# iMX233-OLINUXINO-MINI_Rev_C.net
KiCad netlist of a schematic drawn in EAGLE
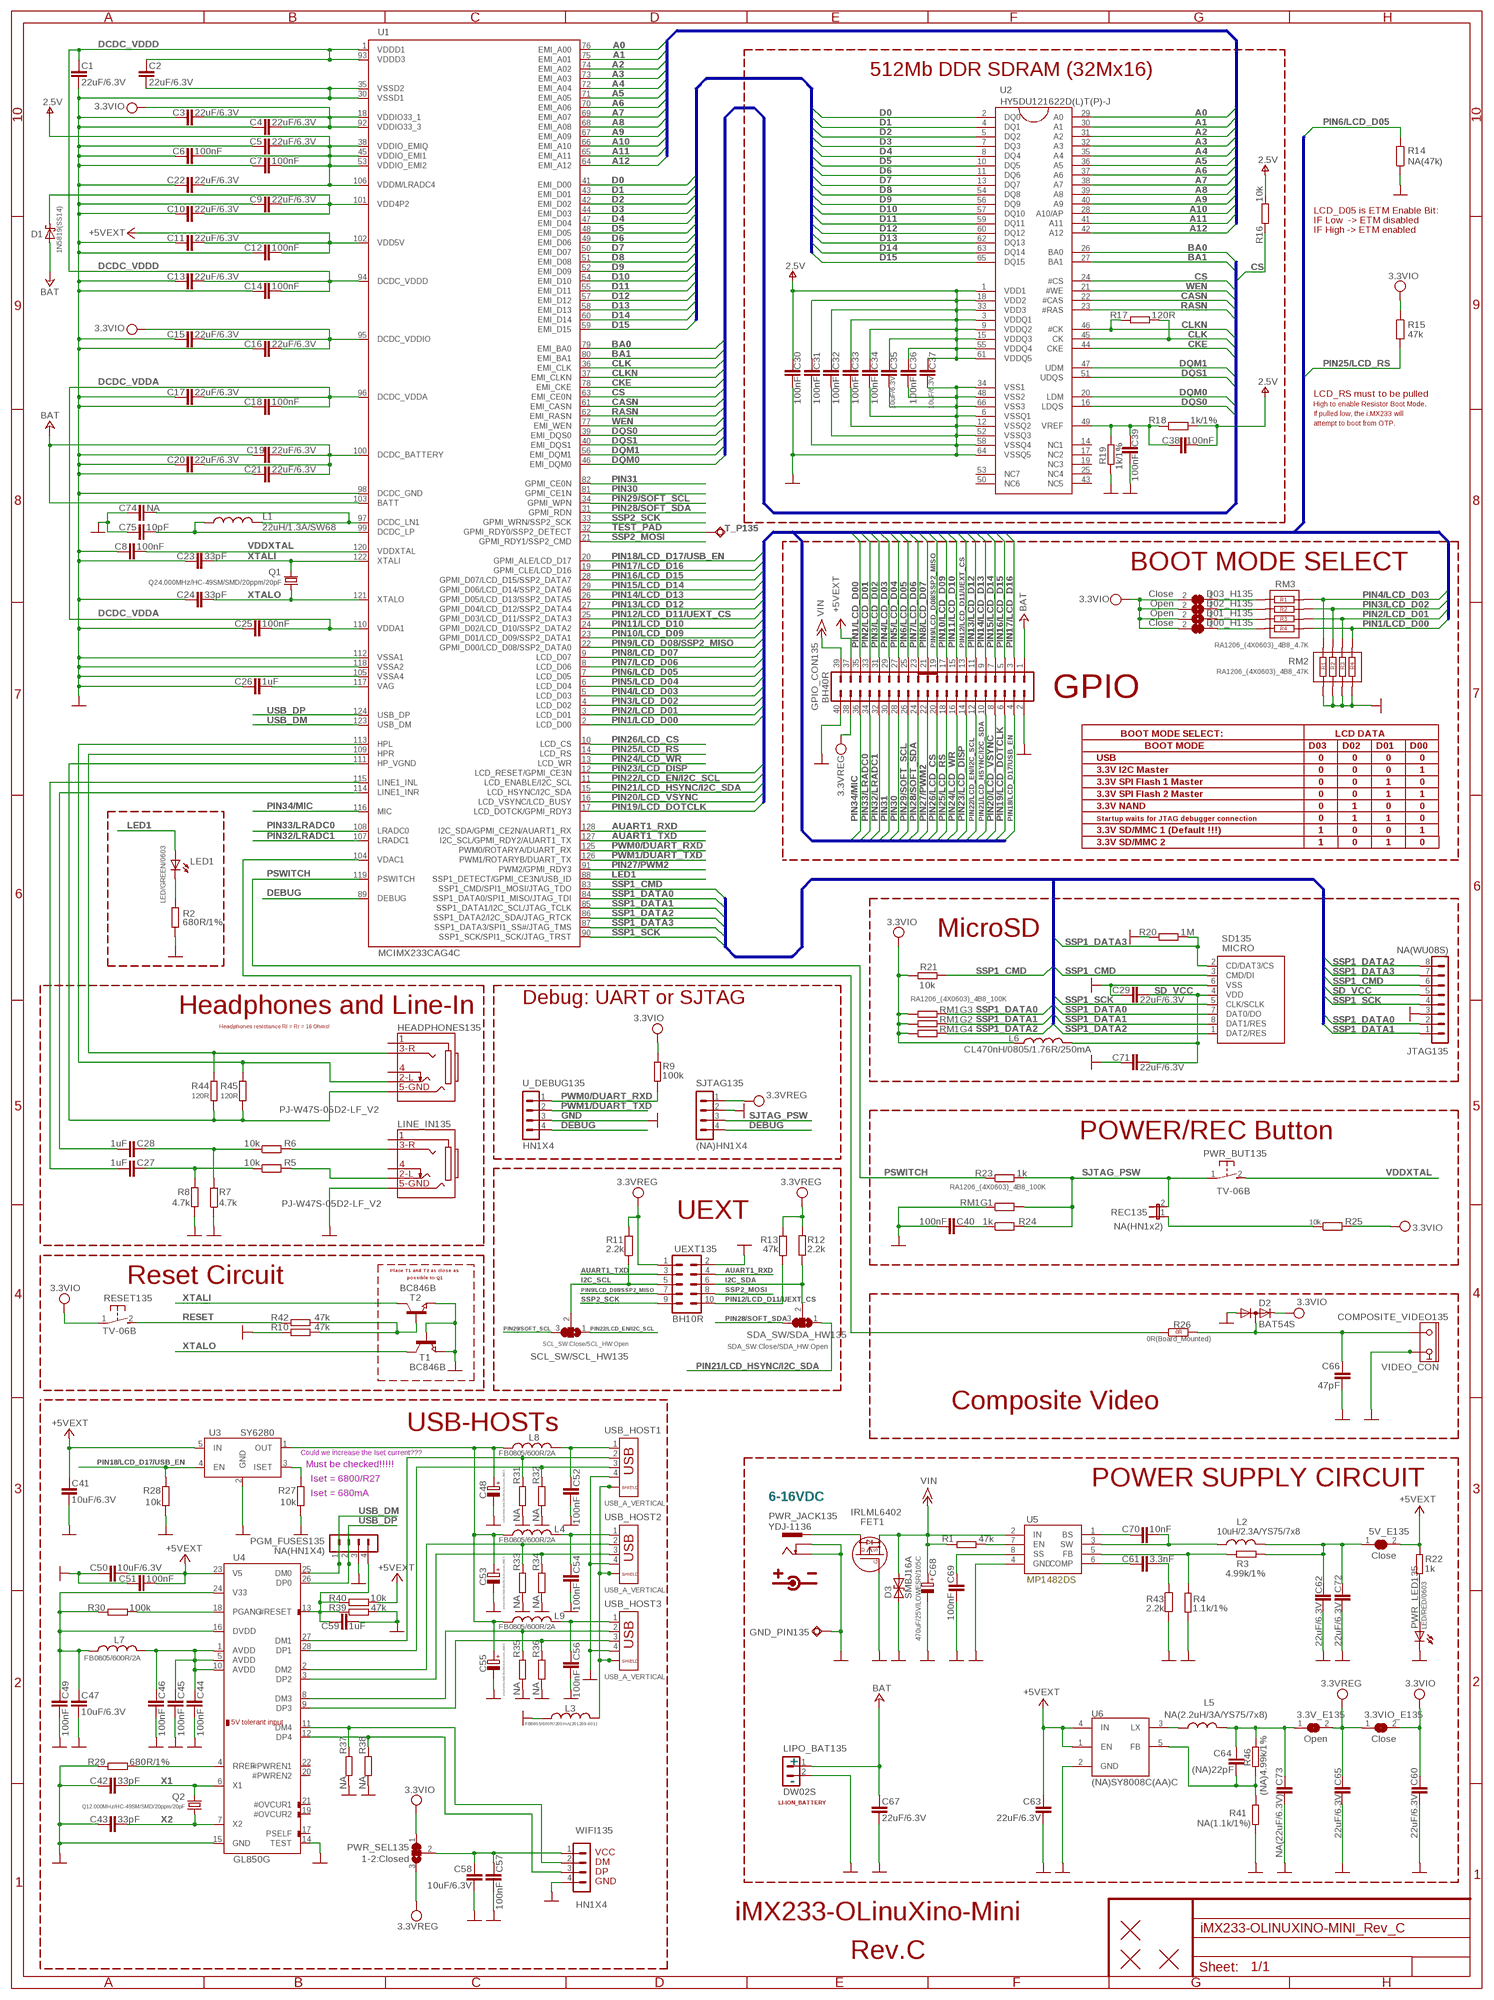
[diagram p0: schematic, sheet 1]

(export (version "E")
  (design (tool "Eeschema 10.0.6"))
  (components
    (comp (ref "3.3VIO_E135")
      (value "Close")
      (footprint "eagle-import:SJ_1_SMALLER")
      (libsource (lib "eagle-import") (part "SJSJ_SMALLER"))
    )
    (comp (ref "3.3V_E135")
      (value "Open")
      (footprint "eagle-import:SJ_1_SMALLER")
      (libsource (lib "eagle-import") (part "SJSJ_SMALLER"))
    )
    (comp (ref "5V_E135")
      (value "Close")
      (footprint "eagle-import:SJ_1_SMALLER_CLOSE")
      (libsource (lib "eagle-import") (part "SJSJ_1_SMALLER_CLOSE"))
    )
    (comp (ref "C1")
      (value "22uF/6.3V")
      (footprint "eagle-import:C0805_5MIL_DWS")
      (libsource (lib "eagle-import") (part "C-EUC0805_5MIL_DWS"))
    )
    (comp (ref "C2")
      (value "22uF/6.3V")
      (footprint "eagle-import:C0805_5MIL_DWS")
      (libsource (lib "eagle-import") (part "C-EUC0805_5MIL_DWS"))
    )
    (comp (ref "C3")
      (value "22uF/6.3V")
      (footprint "eagle-import:C0805_5MIL_DWS")
      (libsource (lib "eagle-import") (part "C-EUC0805_5MIL_DWS"))
    )
    (comp (ref "C4")
      (value "22uF/6.3V")
      (footprint "eagle-import:C0805_5MIL_DWS")
      (libsource (lib "eagle-import") (part "C-EUC0805_5MIL_DWS"))
    )
    (comp (ref "C5")
      (value "22uF/6.3V")
      (footprint "eagle-import:C0805_5MIL_DWS")
      (libsource (lib "eagle-import") (part "C-EUC0805_5MIL_DWS"))
    )
    (comp (ref "C6")
      (value "100nF")
      (footprint "eagle-import:C0603_DWS")
      (libsource (lib "eagle-import") (part "C-EUC0603_DWS"))
    )
    (comp (ref "C7")
      (value "100nF")
      (footprint "eagle-import:C0603_DWS")
      (libsource (lib "eagle-import") (part "C-EUC0603_DWS"))
    )
    (comp (ref "C8")
      (value "100nF")
      (footprint "eagle-import:C0603_DWS")
      (libsource (lib "eagle-import") (part "C-EUC0603_DWS"))
    )
    (comp (ref "C9")
      (value "22uF/6.3V")
      (footprint "eagle-import:C0805_5MIL_DWS")
      (libsource (lib "eagle-import") (part "C-EUC0805_5MIL_DWS"))
    )
    (comp (ref "C10")
      (value "22uF/6.3V")
      (footprint "eagle-import:C0805_5MIL_DWS")
      (libsource (lib "eagle-import") (part "C-EUC0805_5MIL_DWS"))
    )
    (comp (ref "C11")
      (value "22uF/6.3V")
      (footprint "eagle-import:C0805_5MIL_DWS")
      (libsource (lib "eagle-import") (part "C-EUC0805_5MIL_DWS"))
    )
    (comp (ref "C12")
      (value "100nF")
      (footprint "eagle-import:C0603_DWS")
      (libsource (lib "eagle-import") (part "C-EUC0603_DWS"))
    )
    (comp (ref "C13")
      (value "22uF/6.3V")
      (footprint "eagle-import:C0805_5MIL_DWS")
      (libsource (lib "eagle-import") (part "C-EUC0805_5MIL_DWS"))
    )
    (comp (ref "C14")
      (value "100nF")
      (footprint "eagle-import:C0603_DWS")
      (libsource (lib "eagle-import") (part "C-EUC0603_DWS"))
    )
    (comp (ref "C15")
      (value "22uF/6.3V")
      (footprint "eagle-import:C0805_5MIL_DWS")
      (libsource (lib "eagle-import") (part "C-EUC0805_5MIL_DWS"))
    )
    (comp (ref "C16")
      (value "22uF/6.3V")
      (footprint "eagle-import:C0805_5MIL_DWS")
      (libsource (lib "eagle-import") (part "C-EUC0805_5MIL_DWS"))
    )
    (comp (ref "C17")
      (value "22uF/6.3V")
      (footprint "eagle-import:C0805_5MIL_DWS")
      (libsource (lib "eagle-import") (part "C-EUC0805_5MIL_DWS"))
    )
    (comp (ref "C18")
      (value "100nF")
      (footprint "eagle-import:C0603_DWS")
      (libsource (lib "eagle-import") (part "C-EUC0603_DWS"))
    )
    (comp (ref "C19")
      (value "22uF/6.3V")
      (footprint "eagle-import:C0805_5MIL_DWS")
      (libsource (lib "eagle-import") (part "C-EUC0805_5MIL_DWS"))
    )
    (comp (ref "C20")
      (value "22uF/6.3V")
      (footprint "eagle-import:C0805_5MIL_DWS")
      (libsource (lib "eagle-import") (part "C-EUC0805_5MIL_DWS"))
    )
    (comp (ref "C21")
      (value "22uF/6.3V")
      (footprint "eagle-import:C0805_5MIL_DWS")
      (libsource (lib "eagle-import") (part "C-EUC0805_5MIL_DWS"))
    )
    (comp (ref "C22")
      (value "22uF/6.3V")
      (footprint "eagle-import:C0805_5MIL_DWS")
      (libsource (lib "eagle-import") (part "C-EUC0805_5MIL_DWS"))
    )
    (comp (ref "C23")
      (value "33pF")
      (footprint "eagle-import:C0603_DWS")
      (libsource (lib "eagle-import") (part "C-EUC0603_DWS"))
    )
    (comp (ref "C24")
      (value "33pF")
      (footprint "eagle-import:C0603_DWS")
      (libsource (lib "eagle-import") (part "C-EUC0603_DWS"))
    )
    (comp (ref "C25")
      (value "100nF")
      (footprint "eagle-import:C0603_DWS")
      (libsource (lib "eagle-import") (part "C-EUC0603_DWS"))
    )
    (comp (ref "C26")
      (value "1uF")
      (footprint "eagle-import:C0603_DWS")
      (libsource (lib "eagle-import") (part "C-EUC0603_DWS"))
    )
    (comp (ref "C27")
      (value "1uF")
      (footprint "eagle-import:C0603_DWS")
      (libsource (lib "eagle-import") (part "C-EUC0603_DWS"))
    )
    (comp (ref "C28")
      (value "1uF")
      (footprint "eagle-import:C0603_DWS")
      (libsource (lib "eagle-import") (part "C-EUC0603_DWS"))
    )
    (comp (ref "C29")
      (value "22uF/6.3V")
      (footprint "eagle-import:C0805_5MIL_DWS")
      (libsource (lib "eagle-import") (part "C-EUC0805_5MIL_DWS"))
    )
    (comp (ref "C30")
      (value "100nF")
      (footprint "eagle-import:C0603_DWS")
      (libsource (lib "eagle-import") (part "C-EUC0603_DWS"))
    )
    (comp (ref "C31")
      (value "100nF")
      (footprint "eagle-import:C0603_DWS")
      (libsource (lib "eagle-import") (part "C-EUC0603_DWS"))
    )
    (comp (ref "C32")
      (value "100nF")
      (footprint "eagle-import:C0603_DWS")
      (libsource (lib "eagle-import") (part "C-EUC0603_DWS"))
    )
    (comp (ref "C33")
      (value "100nF")
      (footprint "eagle-import:C0603_DWS")
      (libsource (lib "eagle-import") (part "C-EUC0603_DWS"))
    )
    (comp (ref "C34")
      (value "100nF")
      (footprint "eagle-import:C0603_DWS")
      (libsource (lib "eagle-import") (part "C-EUC0603_DWS"))
    )
    (comp (ref "C35")
      (value "10uF/6.3V")
      (footprint "eagle-import:C0603_DWS")
      (libsource (lib "eagle-import") (part "C-EUC0603_DWS"))
    )
    (comp (ref "C36")
      (value "100nF")
      (footprint "eagle-import:C0603_DWS")
      (libsource (lib "eagle-import") (part "C-EUC0603_DWS"))
    )
    (comp (ref "C37")
      (value "10uF/6.3V")
      (footprint "eagle-import:C0603_DWS")
      (libsource (lib "eagle-import") (part "C-EUC0603_DWS"))
    )
    (comp (ref "C38")
      (value "100nF")
      (footprint "eagle-import:C0603_DWS")
      (libsource (lib "eagle-import") (part "C-EUC0603_DWS"))
    )
    (comp (ref "C39")
      (value "100nF")
      (footprint "eagle-import:C0603_DWS")
      (libsource (lib "eagle-import") (part "C-EUC0603_DWS"))
    )
    (comp (ref "C40")
      (value "100nF")
      (footprint "eagle-import:C0603_DWS")
      (libsource (lib "eagle-import") (part "C-EUC0603_DWS"))
    )
    (comp (ref "C41")
      (value "10uF/6.3V")
      (footprint "eagle-import:C0603_DWS")
      (libsource (lib "eagle-import") (part "C-EUC0603_DWS"))
    )
    (comp (ref "C42")
      (value "33pF")
      (footprint "eagle-import:C0603_DWS")
      (libsource (lib "eagle-import") (part "C-EUC0603_DWS"))
    )
    (comp (ref "C43")
      (value "33pF")
      (footprint "eagle-import:C0603_DWS")
      (libsource (lib "eagle-import") (part "C-EUC0603_DWS"))
    )
    (comp (ref "C44")
      (value "100nF")
      (footprint "eagle-import:C0603_DWS")
      (libsource (lib "eagle-import") (part "C-EUC0603_DWS"))
    )
    (comp (ref "C45")
      (value "100nF")
      (footprint "eagle-import:C0603_DWS")
      (libsource (lib "eagle-import") (part "C-EUC0603_DWS"))
    )
    (comp (ref "C46")
      (value "100nF")
      (footprint "eagle-import:C0603_DWS")
      (libsource (lib "eagle-import") (part "C-EUC0603_DWS"))
    )
    (comp (ref "C47")
      (value "10uF/6.3V")
      (footprint "eagle-import:C0603_DWS")
      (libsource (lib "eagle-import") (part "C-EUC0603_DWS"))
    )
    (comp (ref "C48")
      (value "100uF/16V/LOWESR/105C/6.3x11mm_RM2.5")
      (footprint "eagle-import:E2,5-6,3")
      (libsource (lib "eagle-import") (part "CPOL-EUE2.5-6.3"))
    )
    (comp (ref "C49")
      (value "100nF")
      (footprint "eagle-import:C0603_DWS")
      (libsource (lib "eagle-import") (part "C-EUC0603_DWS"))
    )
    (comp (ref "C50")
      (value "10uF/6.3V")
      (footprint "eagle-import:C0603_DWS")
      (libsource (lib "eagle-import") (part "C-EUC0603_DWS"))
    )
    (comp (ref "C51")
      (value "100nF")
      (footprint "eagle-import:C0603_DWS")
      (libsource (lib "eagle-import") (part "C-EUC0603_DWS"))
    )
    (comp (ref "C52")
      (value "100nF")
      (footprint "eagle-import:C0603_DWS")
      (libsource (lib "eagle-import") (part "C-EUC0603_DWS"))
    )
    (comp (ref "C53")
      (value "100uF/16V/LOWESR/105C/6.3x11mm_RM2.5")
      (footprint "eagle-import:E2,5-6,3")
      (libsource (lib "eagle-import") (part "CPOL-EUE2.5-6.3"))
    )
    (comp (ref "C54")
      (value "100nF")
      (footprint "eagle-import:C0603_DWS")
      (libsource (lib "eagle-import") (part "C-EUC0603_DWS"))
    )
    (comp (ref "C55")
      (value "100uF/16V/LOWESR/105C/6.3x11mm_RM2.5")
      (footprint "eagle-import:E2,5-6,3")
      (libsource (lib "eagle-import") (part "CPOL-EUE2.5-6.3"))
    )
    (comp (ref "C56")
      (value "100nF")
      (footprint "eagle-import:C0603_DWS")
      (libsource (lib "eagle-import") (part "C-EUC0603_DWS"))
    )
    (comp (ref "C57")
      (value "100nF")
      (footprint "eagle-import:C0603_DWS")
      (libsource (lib "eagle-import") (part "C-EUC0603_DWS"))
    )
    (comp (ref "C58")
      (value "10uF/6.3V")
      (footprint "eagle-import:C0603_DWS")
      (libsource (lib "eagle-import") (part "C-EUC0603_DWS"))
    )
    (comp (ref "C59")
      (value "1uF")
      (footprint "eagle-import:C0603_DWS")
      (libsource (lib "eagle-import") (part "C-EUC0603_DWS"))
    )
    (comp (ref "C60")
      (value "22uF/6.3V")
      (footprint "eagle-import:C0805_5MIL_DWS")
      (libsource (lib "eagle-import") (part "C-EUC0805_5MIL_DWS"))
    )
    (comp (ref "C61")
      (value "3.3nF")
      (footprint "eagle-import:C0603_DWS")
      (libsource (lib "eagle-import") (part "C-EUC0603_DWS"))
    )
    (comp (ref "C62")
      (value "22uF/6.3V")
      (footprint "eagle-import:C0805_5MIL_DWS")
      (libsource (lib "eagle-import") (part "C-EUC0805_5MIL_DWS"))
    )
    (comp (ref "C63")
      (value "22uF/6.3V")
      (footprint "eagle-import:C0805_5MIL_DWS")
      (libsource (lib "eagle-import") (part "C-EUC0805_5MIL_DWS"))
    )
    (comp (ref "C64")
      (value "(NA)22pF")
      (footprint "eagle-import:C0603_DWS")
      (libsource (lib "eagle-import") (part "C-EUC0603_DWS"))
    )
    (comp (ref "C65")
      (value "22uF/6.3V")
      (footprint "eagle-import:C0805_5MIL_DWS")
      (libsource (lib "eagle-import") (part "C-EUC0805_5MIL_DWS"))
    )
    (comp (ref "C66")
      (value "47pF")
      (footprint "eagle-import:C0603_DWS")
      (libsource (lib "eagle-import") (part "C-EUC0603_DWS"))
    )
    (comp (ref "C67")
      (value "22uF/6.3V")
      (footprint "eagle-import:C0805_5MIL_DWS")
      (libsource (lib "eagle-import") (part "C-EUC0805_5MIL_DWS"))
    )
    (comp (ref "C68")
      (value "470uF/25V/LOWESR/105C")
      (footprint "eagle-import:E5-10,5")
      (libsource (lib "eagle-import") (part "CPOL-EUE5-10.5"))
    )
    (comp (ref "C69")
      (value "100nF")
      (footprint "eagle-import:C0603_DWS")
      (libsource (lib "eagle-import") (part "C-EUC0603_DWS"))
    )
    (comp (ref "C70")
      (value "10nF")
      (footprint "eagle-import:C0603_DWS")
      (libsource (lib "eagle-import") (part "C-EUC0603_DWS"))
    )
    (comp (ref "C71")
      (value "22uF/6.3V")
      (footprint "eagle-import:C0805_5MIL_DWS")
      (libsource (lib "eagle-import") (part "C-EUC0805_5MIL_DWS"))
    )
    (comp (ref "C72")
      (value "22uF/6.3V")
      (footprint "eagle-import:C0805_5MIL_DWS")
      (libsource (lib "eagle-import") (part "C-EUC0805_5MIL_DWS"))
    )
    (comp (ref "C73")
      (value "NA(22uF/6.3V)")
      (footprint "eagle-import:C0805_5MIL_DWS")
      (libsource (lib "eagle-import") (part "C-EUC0805_5MIL_DWS"))
    )
    (comp (ref "C74")
      (value "NA")
      (footprint "eagle-import:C0603_DWS")
      (libsource (lib "eagle-import") (part "C-EUC0603_DWS"))
    )
    (comp (ref "C75")
      (value "10pF")
      (footprint "eagle-import:C0603_DWS")
      (libsource (lib "eagle-import") (part "C-EUC0603_DWS"))
    )
    (comp (ref "COMPOSITE_VIDEO135")
      (value "VIDEO_CON")
      (footprint "eagle-import:VIDEO_CON")
      (libsource (lib "eagle-import") (part "VIDEO_CON1"))
    )
    (comp (ref "D00_H135")
      (value "Close")
      (footprint "eagle-import:SJ_1_SMALLER")
      (libsource (lib "eagle-import") (part "SJSJ_SMALLER"))
    )
    (comp (ref "D1")
      (value "1N5819(SS14)")
      (footprint "eagle-import:MLL-41")
      (libsource (lib "eagle-import") (part "SCHOTKKY7.62SS2"))
    )
    (comp (ref "D01_H135")
      (value "Open")
      (footprint "eagle-import:SJ_1_SMALLER")
      (libsource (lib "eagle-import") (part "SJSJ_SMALLER"))
    )
    (comp (ref "D2")
      (value "BAT54S")
      (footprint "eagle-import:SOT23C(BAT54S)")
      (libsource (lib "eagle-import") (part "DIODE_AC-AC_"))
    )
    (comp (ref "D02_H135")
      (value "Open")
      (footprint "eagle-import:SJ_1_SMALLER")
      (libsource (lib "eagle-import") (part "SJSJ_SMALLER"))
    )
    (comp (ref "D3")
      (value "SMBJ16A")
      (footprint "eagle-import:DO214AA")
      (libsource (lib "eagle-import") (part "SMBJ15A"))
    )
    (comp (ref "D03_H135")
      (value "Close")
      (footprint "eagle-import:SJ_1_SMALLER")
      (libsource (lib "eagle-import") (part "SJSJ_SMALLER"))
    )
    (comp (ref "FET1")
      (value "IRLML6402")
      (footprint "eagle-import:SOT23")
      (libsource (lib "eagle-import") (part "P-MOS+DIODIRLML6402"))
    )
    (comp (ref "GND_PIN135")
      (value "TESTPAD3")
      (footprint "eagle-import:TEST_PAD40_70_SQUARE")
      (libsource (lib "eagle-import") (part "TESTPAD3"))
    )
    (comp (ref "GPIO_CON135")
      (value "BH40R")
      (footprint "eagle-import:BH40R")
      (libsource (lib "eagle-import") (part "ML40R"))
    )
    (comp (ref "HEADPHONES135")
      (value "PJ-W47S-05D2-LF_V2")
      (footprint "eagle-import:PJ-W47S-05D2-LF_5PIN_V2")
      (libsource (lib "eagle-import") (part "AUDIO_JACK_5PINPJ-W47S-05D2-LF_V2"))
    )
    (comp (ref "JTAG135")
      (value "NA(WU08S)")
      (footprint "eagle-import:WU08S")
      (libsource (lib "eagle-import") (part "CON8WU08S"))
    )
    (comp (ref "L1")
      (value "22uH/1.3A/SW68")
      (footprint "eagle-import:CD53")
      (libsource (lib "eagle-import") (part "L-USL_CD53"))
    )
    (comp (ref "L2")
      (value "10uH/2.3A/YS75/7x8")
      (footprint "eagle-import:8X8MM_3131")
      (libsource (lib "eagle-import") (part "LLQH88PN100M38"))
    )
    (comp (ref "L3")
      (value "FB0805/600R/200mA(201209-601)")
      (footprint "eagle-import:L0805_5MIL_DWS")
      (libsource (lib "eagle-import") (part "L-USL0805_5MIL_DWS"))
    )
    (comp (ref "L4")
      (value "FB0805/600R/2A")
      (footprint "eagle-import:L0805_5MIL_DWS")
      (libsource (lib "eagle-import") (part "L-USL0805_5MIL_DWS"))
    )
    (comp (ref "L5")
      (value "NA(2.2uH/3A/YS75/7x8)")
      (footprint "eagle-import:8X8MM_3131")
      (libsource (lib "eagle-import") (part "LLQH88PN100M38"))
    )
    (comp (ref "L6")
      (value "CL470nH/0805/1.76R/250mA")
      (footprint "eagle-import:L0805_5MIL_DWS")
      (libsource (lib "eagle-import") (part "L-USL0805_5MIL_DWS"))
    )
    (comp (ref "L7")
      (value "FB0805/600R/2A")
      (footprint "eagle-import:L0805_5MIL_DWS")
      (libsource (lib "eagle-import") (part "L-USL0805_5MIL_DWS"))
    )
    (comp (ref "L8")
      (value "FB0805/600R/2A")
      (footprint "eagle-import:L0805_5MIL_DWS")
      (libsource (lib "eagle-import") (part "L-USL0805_5MIL_DWS"))
    )
    (comp (ref "L9")
      (value "FB0805/600R/2A")
      (footprint "eagle-import:L0805_5MIL_DWS")
      (libsource (lib "eagle-import") (part "L-USL0805_5MIL_DWS"))
    )
    (comp (ref "LED1")
      (value "LED/GREEN/0603")
      (footprint "eagle-import:LED-0603")
      (libsource (lib "eagle-import") (part "LED0603DWS"))
    )
    (comp (ref "LINE_IN135")
      (value "PJ-W47S-05D2-LF_V2")
      (footprint "eagle-import:PJ-W47S-05D2-LF_5PIN_V2")
      (libsource (lib "eagle-import") (part "AUDIO_JACK_5PINPJ-W47S-05D2-LF_V2"))
    )
    (comp (ref "LIPO_BAT135")
      (value "DW02S")
      (footprint "eagle-import:DW02S")
      (libsource (lib "eagle-import") (part "CON2DW02S"))
    )
    (comp (ref "PGM_FUSES135")
      (value "NA(HN1X4)")
      (footprint "eagle-import:HN1X4")
      (libsource (lib "eagle-import") (part "CON4HN1X4"))
    )
    (comp (ref "PWR_BUT135")
      (value "TV-06B")
      (footprint "eagle-import:B3F-31XX")
      (libsource (lib "eagle-import") (part "31-XX"))
    )
    (comp (ref "PWR_JACK135")
      (value "YDJ-1136")
      (footprint "eagle-import:PWR_JACK_UNI_MILLING")
      (libsource (lib "eagle-import") (part "PWR-JAKPWR_JACK_UNI_MILLING"))
    )
    (comp (ref "PWR_LED135")
      (value "LED/RED/0603")
      (footprint "eagle-import:LED-0603")
      (libsource (lib "eagle-import") (part "LED0603DWS"))
    )
    (comp (ref "PWR_SEL135")
      (value "1-2:Closed")
      (footprint "eagle-import:SJ_2_SMALL")
      (libsource (lib "eagle-import") (part "SJ2W3"))
    )
    (comp (ref "Q1")
      (value "Q24.000MHz/HC-49SM/SMD/20ppm/20pF")
      (footprint "eagle-import:HC49_SMD2_THIN")
      (libsource (lib "eagle-import") (part "HC49/S1"))
    )
    (comp (ref "Q2")
      (value "Q12.000MHz/HC-49SM/SMD/20ppm/20pF")
      (footprint "eagle-import:HC49_SMD2_THIN")
      (libsource (lib "eagle-import") (part "HC49/S1"))
    )
    (comp (ref "R1")
      (value "47k")
      (footprint "eagle-import:R0603_5MIL_DWS")
      (libsource (lib "eagle-import") (part "R-EU_R0603_5MIL_DWS"))
    )
    (comp (ref "R2")
      (value "680R/1%")
      (footprint "eagle-import:R0603_5MIL_DWS")
      (libsource (lib "eagle-import") (part "R-EU_R0603_5MIL_DWS"))
    )
    (comp (ref "R3")
      (value "4.99k/1%")
      (footprint "eagle-import:R0603_5MIL_DWS")
      (libsource (lib "eagle-import") (part "R-EU_R0603_5MIL_DWS"))
    )
    (comp (ref "R4")
      (value "1.1k/1%")
      (footprint "eagle-import:R0603_5MIL_DWS")
      (libsource (lib "eagle-import") (part "R-EU_R0603_5MIL_DWS"))
    )
    (comp (ref "R5")
      (value "10k")
      (footprint "eagle-import:R0603_5MIL_DWS")
      (libsource (lib "eagle-import") (part "R-EU_R0603_5MIL_DWS"))
    )
    (comp (ref "R6")
      (value "10k")
      (footprint "eagle-import:R0603_5MIL_DWS")
      (libsource (lib "eagle-import") (part "R-EU_R0603_5MIL_DWS"))
    )
    (comp (ref "R7")
      (value "4.7k")
      (footprint "eagle-import:R0603_5MIL_DWS")
      (libsource (lib "eagle-import") (part "R-EU_R0603_5MIL_DWS"))
    )
    (comp (ref "R8")
      (value "4.7k")
      (footprint "eagle-import:R0603_5MIL_DWS")
      (libsource (lib "eagle-import") (part "R-EU_R0603_5MIL_DWS"))
    )
    (comp (ref "R9")
      (value "100k")
      (footprint "eagle-import:R0603_5MIL_DWS")
      (libsource (lib "eagle-import") (part "R-EU_R0603_5MIL_DWS"))
    )
    (comp (ref "R10")
      (value "47k")
      (footprint "eagle-import:R0603_5MIL_DWS")
      (libsource (lib "eagle-import") (part "R-EU_R0603_5MIL_DWS"))
    )
    (comp (ref "R11")
      (value "2.2k")
      (footprint "eagle-import:R0603_5MIL_DWS")
      (libsource (lib "eagle-import") (part "R-EU_R0603_5MIL_DWS"))
    )
    (comp (ref "R12")
      (value "2.2k")
      (footprint "eagle-import:R0603_5MIL_DWS")
      (libsource (lib "eagle-import") (part "R-EU_R0603_5MIL_DWS"))
    )
    (comp (ref "R13")
      (value "47k")
      (footprint "eagle-import:R0603_5MIL_DWS")
      (libsource (lib "eagle-import") (part "R-EU_R0603_5MIL_DWS"))
    )
    (comp (ref "R14")
      (value "NA(47k)")
      (footprint "eagle-import:R0603_5MIL_DWS")
      (libsource (lib "eagle-import") (part "R-EU_R0603_5MIL_DWS"))
    )
    (comp (ref "R15")
      (value "47k")
      (footprint "eagle-import:R0603_5MIL_DWS")
      (libsource (lib "eagle-import") (part "R-EU_R0603_5MIL_DWS"))
    )
    (comp (ref "R16")
      (value "10k")
      (footprint "eagle-import:R0603_5MIL_DWS")
      (libsource (lib "eagle-import") (part "R-EU_R0603_5MIL_DWS"))
    )
    (comp (ref "R17")
      (value "120R")
      (footprint "eagle-import:R0603_5MIL_DWS")
      (libsource (lib "eagle-import") (part "R-EU_R0603_5MIL_DWS"))
    )
    (comp (ref "R18")
      (value "1k/1%")
      (footprint "eagle-import:R0603_5MIL_DWS")
      (libsource (lib "eagle-import") (part "R-EU_R0603_5MIL_DWS"))
    )
    (comp (ref "R19")
      (value "1k/1%")
      (footprint "eagle-import:R0603_5MIL_DWS")
      (libsource (lib "eagle-import") (part "R-EU_R0603_5MIL_DWS"))
    )
    (comp (ref "R20")
      (value "1M")
      (footprint "eagle-import:R0603_5MIL_DWS")
      (libsource (lib "eagle-import") (part "R-EU_R0603_5MIL_DWS"))
    )
    (comp (ref "R21")
      (value "10k")
      (footprint "eagle-import:R0603_5MIL_DWS")
      (libsource (lib "eagle-import") (part "R-EU_R0603_5MIL_DWS"))
    )
    (comp (ref "R22")
      (value "1k")
      (footprint "eagle-import:R0603_5MIL_DWS")
      (libsource (lib "eagle-import") (part "R-EU_R0603_5MIL_DWS"))
    )
    (comp (ref "R23")
      (value "1k")
      (footprint "eagle-import:R0603_5MIL_DWS")
      (libsource (lib "eagle-import") (part "R-EU_R0603_5MIL_DWS"))
    )
    (comp (ref "R24")
      (value "1k")
      (footprint "eagle-import:R0603_5MIL_DWS")
      (libsource (lib "eagle-import") (part "R-EU_R0603_5MIL_DWS"))
    )
    (comp (ref "R25")
      (value "10k")
      (footprint "eagle-import:R0603_5MIL_DWS_NA")
      (libsource (lib "eagle-import") (part "R-EU_R0603_5MIL_DWS_NA"))
    )
    (comp (ref "R26")
      (value "0R(Board_Mounted)")
      (footprint "eagle-import:0603_0R")
      (libsource (lib "eagle-import") (part "R_0R0R(NA)"))
    )
    (comp (ref "R27")
      (value "10k")
      (footprint "eagle-import:R0603_5MIL_DWS")
      (libsource (lib "eagle-import") (part "R-EU_R0603_5MIL_DWS"))
    )
    (comp (ref "R28")
      (value "10k")
      (footprint "eagle-import:R0603_5MIL_DWS")
      (libsource (lib "eagle-import") (part "R-EU_R0603_5MIL_DWS"))
    )
    (comp (ref "R29")
      (value "680R/1%")
      (footprint "eagle-import:R0603_5MIL_DWS")
      (libsource (lib "eagle-import") (part "R-EU_R0603_5MIL_DWS"))
    )
    (comp (ref "R30")
      (value "100k")
      (footprint "eagle-import:R0603_5MIL_DWS")
      (libsource (lib "eagle-import") (part "R-EU_R0603_5MIL_DWS"))
    )
    (comp (ref "R31")
      (value "NA")
      (footprint "eagle-import:R0603_5MIL_DWS")
      (libsource (lib "eagle-import") (part "R-EU_R0603_5MIL_DWS"))
    )
    (comp (ref "R32")
      (value "NA")
      (footprint "eagle-import:R0603_5MIL_DWS")
      (libsource (lib "eagle-import") (part "R-EU_R0603_5MIL_DWS"))
    )
    (comp (ref "R33")
      (value "NA")
      (footprint "eagle-import:R0603_5MIL_DWS")
      (libsource (lib "eagle-import") (part "R-EU_R0603_5MIL_DWS"))
    )
    (comp (ref "R34")
      (value "NA")
      (footprint "eagle-import:R0603_5MIL_DWS")
      (libsource (lib "eagle-import") (part "R-EU_R0603_5MIL_DWS"))
    )
    (comp (ref "R35")
      (value "NA")
      (footprint "eagle-import:R0603_5MIL_DWS")
      (libsource (lib "eagle-import") (part "R-EU_R0603_5MIL_DWS"))
    )
    (comp (ref "R36")
      (value "NA")
      (footprint "eagle-import:R0603_5MIL_DWS")
      (libsource (lib "eagle-import") (part "R-EU_R0603_5MIL_DWS"))
    )
    (comp (ref "R37")
      (value "NA")
      (footprint "eagle-import:R0603_5MIL_DWS")
      (libsource (lib "eagle-import") (part "R-EU_R0603_5MIL_DWS"))
    )
    (comp (ref "R38")
      (value "NA")
      (footprint "eagle-import:R0603_5MIL_DWS")
      (libsource (lib "eagle-import") (part "R-EU_R0603_5MIL_DWS"))
    )
    (comp (ref "R39")
      (value "47k")
      (footprint "eagle-import:R0603_5MIL_DWS")
      (libsource (lib "eagle-import") (part "R-EU_R0603_5MIL_DWS"))
    )
    (comp (ref "R40")
      (value "10k")
      (footprint "eagle-import:R0603_5MIL_DWS")
      (libsource (lib "eagle-import") (part "R-EU_R0603_5MIL_DWS"))
    )
    (comp (ref "R41")
      (value "NA(1.1k/1%)")
      (footprint "eagle-import:R0603_5MIL_DWS")
      (libsource (lib "eagle-import") (part "R-EU_R0603_5MIL_DWS"))
    )
    (comp (ref "R42")
      (value "47k")
      (footprint "eagle-import:R0603_5MIL_DWS")
      (libsource (lib "eagle-import") (part "R-EU_R0603_5MIL_DWS"))
    )
    (comp (ref "R43")
      (value "2.2k")
      (footprint "eagle-import:R0603_5MIL_DWS")
      (libsource (lib "eagle-import") (part "R-EU_R0603_5MIL_DWS"))
    )
    (comp (ref "R44")
      (value "120R")
      (footprint "eagle-import:R0603_5MIL_DWS")
      (libsource (lib "eagle-import") (part "R-EU_R0603_5MIL_DWS"))
    )
    (comp (ref "R45")
      (value "120R")
      (footprint "eagle-import:R0603_5MIL_DWS")
      (libsource (lib "eagle-import") (part "R-EU_R0603_5MIL_DWS"))
    )
    (comp (ref "R46")
      (value "(NA)4.99k/1%")
      (footprint "eagle-import:R0603_5MIL_DWS")
      (libsource (lib "eagle-import") (part "R-EU_R0603_5MIL_DWS"))
    )
    (comp (ref "REC135")
      (value "NA(HN1x2)")
      (footprint "eagle-import:JP1")
      (libsource (lib "eagle-import") (part "JP1E"))
    )
    (comp (ref "RESET135")
      (value "TV-06B")
      (footprint "eagle-import:B3F-31XX")
      (libsource (lib "eagle-import") (part "31-XX"))
    )
    (comp (ref "RM1")
      (value "RA1206_(4X0603)_4B8_100K")
      (footprint "eagle-import:R_MATRIX_4")
      (libsource (lib "eagle-import") (part "R_MATRIX_4E"))
    )
    (comp (ref "RM2")
      (value "RA1206_(4X0603)_4B8_47K")
      (footprint "eagle-import:R_MATRIX_4")
      (libsource (lib "eagle-import") (part "R_MATRIX_4"))
    )
    (comp (ref "RM3")
      (value "RA1206_(4X0603)_4B8_4.7K")
      (footprint "eagle-import:R_MATRIX_4")
      (libsource (lib "eagle-import") (part "R_MATRIX_4"))
    )
    (comp (ref "SCL_SW/SCL_HW135")
      (value "SCL_SW:Close/SCL_HW:Open")
      (footprint "eagle-import:SJ_2_SMALLER")
      (libsource (lib "eagle-import") (part "SJ2W4"))
    )
    (comp (ref "SD135")
      (value "MICRO")
      (footprint "eagle-import:TFR-MEM-CON")
      (libsource (lib "eagle-import") (part "MICRO_SD/MMC"))
    )
    (comp (ref "SDA_SW/SDA_HW135")
      (value "SDA_SW:Close/SDA_HW:Open")
      (footprint "eagle-import:SJ_2_SMALLER")
      (libsource (lib "eagle-import") (part "SJ2W4"))
    )
    (comp (ref "SJTAG135")
      (value "(NA)HN1X4")
      (footprint "eagle-import:HN1X4")
      (libsource (lib "eagle-import") (part "CON4HN1X4"))
    )
    (comp (ref "T1")
      (value "BC846B")
      (footprint "eagle-import:SOT23")
      (libsource (lib "eagle-import") (part "NPN-TRANSISTOR_SOT23"))
    )
    (comp (ref "T2")
      (value "BC846B")
      (footprint "eagle-import:SOT23")
      (libsource (lib "eagle-import") (part "NPN-TRANSISTOR_SOT23"))
    )
    (comp (ref "T_P135")
      (value "TESTPAD50/40")
      (footprint "eagle-import:SMD50_40")
      (libsource (lib "eagle-import") (part "TESTPAD50/40"))
    )
    (comp (ref "U$1")
      (value "FIDUCIAL1X2")
      (footprint "eagle-import:FIDUCIAL-1X2")
      (libsource (lib "eagle-import") (part "FIDUCIAL1X2"))
    )
    (comp (ref "U$2")
      (value "FIDUCIAL1X2")
      (footprint "eagle-import:FIDUCIAL-1X2")
      (libsource (lib "eagle-import") (part "FIDUCIAL1X2"))
    )
    (comp (ref "U$3")
      (value "FIDUCIAL1X2")
      (footprint "eagle-import:FIDUCIAL-1X2")
      (libsource (lib "eagle-import") (part "FIDUCIAL1X2"))
    )
    (comp (ref "U1")
      (value "MCIMX233CAG4C")
      (footprint "eagle-import:TQFP128LD")
      (libsource (lib "eagle-import") (part "MCIMX233DAG4B_LD"))
    )
    (comp (ref "U2")
      (value "HY5DU121622D(L)T(P)-J")
      (footprint "eagle-import:66TSOP-II")
      (libsource (lib "eagle-import") (part "HY5DU121622D(L)T(P)-J"))
    )
    (comp (ref "U3")
      (value "SY6280")
      (footprint "eagle-import:SOT23-5")
      (libsource (lib "eagle-import") (part "SY6280"))
    )
    (comp (ref "U4")
      (value "GL850G")
      (footprint "eagle-import:SSOP28")
      (libsource (lib "eagle-import") (part "GL850G"))
    )
    (comp (ref "U5")
      (value "MP1482DS")
      (footprint "eagle-import:SOIC8")
      (libsource (lib "eagle-import") (part "MP1482"))
    )
    (comp (ref "U6")
      (value "(NA)SY8008C(AA)C")
      (footprint "eagle-import:SOT23-5")
      (libsource (lib "eagle-import") (part "SY8008"))
    )
    (comp (ref "UEXT135")
      (value "BH10R")
      (footprint "eagle-import:BH10R")
      (libsource (lib "eagle-import") (part "ML10R"))
    )
    (comp (ref "USB_HOST1")
      (value "USB_A_VERTICAL")
      (footprint "eagle-import:USB_A_VERTICAL_PTH")
      (libsource (lib "eagle-import") (part "USB_SHIELDUSB_A_VERTICAL"))
    )
    (comp (ref "USB_HOST2")
      (value "USB_A_VERTICAL")
      (footprint "eagle-import:USB_A_VERTICAL_PTH")
      (libsource (lib "eagle-import") (part "USB_SHIELDUSB_A_VERTICAL"))
    )
    (comp (ref "USB_HOST3")
      (value "USB_A_VERTICAL")
      (footprint "eagle-import:USB_A_VERTICAL_PTH")
      (libsource (lib "eagle-import") (part "USB_SHIELDUSB_A_VERTICAL"))
    )
    (comp (ref "U_DEBUG135")
      (value "HN1X4")
      (footprint "eagle-import:HN1X4")
      (libsource (lib "eagle-import") (part "CON4HN1X4"))
    )
    (comp (ref "WIFI135")
      (value "HN1X4")
      (footprint "eagle-import:HN1X4")
      (libsource (lib "eagle-import") (part "CON4HN1X4"))
    )
  )
  (nets
    (net (code "1") (name "+5VEXT") (class "Default")
      (node (ref "5V_E135") (pin "2") (pinfunction "2_2") (pintype "passive"))
      (node (ref "C11") (pin "2") (pinfunction "2_2") (pintype "passive"))
      (node (ref "C12") (pin "2") (pinfunction "2_2") (pintype "passive"))
      (node (ref "C41") (pin "1") (pinfunction "1_1") (pintype "passive"))
      (node (ref "C50") (pin "1") (pinfunction "1_1") (pintype "passive"))
      (node (ref "C51") (pin "1") (pinfunction "1_1") (pintype "passive"))
      (node (ref "C63") (pin "1") (pinfunction "1_1") (pintype "passive"))
      (node (ref "GPIO_CON135") (pin "37") (pinfunction "37_37") (pintype "passive"))
      (node (ref "R22") (pin "1") (pinfunction "1_1") (pintype "passive"))
      (node (ref "R40") (pin "2") (pinfunction "2_2") (pintype "passive"))
      (node (ref "U1") (pin "102") (pinfunction "VDD5V_102") (pintype "power_in"))
      (node (ref "U3") (pin "5") (pinfunction "IN_5") (pintype "power_in"))
      (node (ref "U4") (pin "23") (pinfunction "V5_23") (pintype "power_in"))
      (node (ref "U6") (pin "1") (pinfunction "EN_1") (pintype "bidirectional"))
      (node (ref "U6") (pin "4") (pinfunction "IN_4") (pintype "bidirectional"))
    )
    (net (code "2") (name "/A0") (class "Default")
      (node (ref "U1") (pin "76") (pinfunction "EMI_A00_76") (pintype "bidirectional"))
      (node (ref "U2") (pin "29") (pinfunction "A0_29") (pintype "input"))
    )
    (net (code "3") (name "/A1") (class "Default")
      (node (ref "U1") (pin "75") (pinfunction "EMI_A01_75") (pintype "bidirectional"))
      (node (ref "U2") (pin "30") (pinfunction "A1_30") (pintype "input"))
    )
    (net (code "4") (name "/A2") (class "Default")
      (node (ref "U1") (pin "74") (pinfunction "EMI_A02_74") (pintype "bidirectional"))
      (node (ref "U2") (pin "31") (pinfunction "A2_31") (pintype "input"))
    )
    (net (code "5") (name "/A3") (class "Default")
      (node (ref "U1") (pin "73") (pinfunction "EMI_A03_73") (pintype "bidirectional"))
      (node (ref "U2") (pin "32") (pinfunction "A3_32") (pintype "input"))
    )
    (net (code "6") (name "/A4") (class "Default")
      (node (ref "U1") (pin "72") (pinfunction "EMI_A04_72") (pintype "bidirectional"))
      (node (ref "U2") (pin "35") (pinfunction "A4_35") (pintype "input"))
    )
    (net (code "7") (name "/A5") (class "Default")
      (node (ref "U1") (pin "71") (pinfunction "EMI_A05_71") (pintype "bidirectional"))
      (node (ref "U2") (pin "36") (pinfunction "A5_36") (pintype "input"))
    )
    (net (code "8") (name "/A6") (class "Default")
      (node (ref "U1") (pin "70") (pinfunction "EMI_A06_70") (pintype "bidirectional"))
      (node (ref "U2") (pin "37") (pinfunction "A6_37") (pintype "input"))
    )
    (net (code "9") (name "/A7") (class "Default")
      (node (ref "U1") (pin "69") (pinfunction "EMI_A07_69") (pintype "bidirectional"))
      (node (ref "U2") (pin "38") (pinfunction "A7_38") (pintype "input"))
    )
    (net (code "10") (name "/A8") (class "Default")
      (node (ref "U1") (pin "68") (pinfunction "EMI_A08_68") (pintype "bidirectional"))
      (node (ref "U2") (pin "39") (pinfunction "A8_39") (pintype "input"))
    )
    (net (code "11") (name "/A9") (class "Default")
      (node (ref "U1") (pin "67") (pinfunction "EMI_A09_67") (pintype "bidirectional"))
      (node (ref "U2") (pin "40") (pinfunction "A9_40") (pintype "input"))
    )
    (net (code "12") (name "/A10") (class "Default")
      (node (ref "U1") (pin "66") (pinfunction "EMI_A10_66") (pintype "bidirectional"))
      (node (ref "U2") (pin "28") (pinfunction "A10/AP_28") (pintype "input"))
    )
    (net (code "13") (name "/A11") (class "Default")
      (node (ref "U1") (pin "65") (pinfunction "EMI_A11_65") (pintype "bidirectional"))
      (node (ref "U2") (pin "41") (pinfunction "A11_41") (pintype "input"))
    )
    (net (code "14") (name "/A12") (class "Default")
      (node (ref "U1") (pin "64") (pinfunction "EMI_A12_64") (pintype "bidirectional"))
      (node (ref "U2") (pin "42") (pinfunction "A12_42") (pintype "input"))
    )
    (net (code "15") (name "/AUART1_RXD") (class "Default")
      (node (ref "U1") (pin "128") (pinfunction "I2C_SDA/GPMI_CE2N/AUART1_RX_128") (pintype "bidirectional"))
      (node (ref "UEXT135") (pin "4") (pinfunction "4_4") (pintype "passive"))
    )
    (net (code "16") (name "/AUART1_TXD") (class "Default")
      (node (ref "U1") (pin "127") (pinfunction "I2C_SCL/GPMI_RDY2/AUART1_TX_127") (pintype "bidirectional"))
      (node (ref "UEXT135") (pin "3") (pinfunction "3_3") (pintype "passive"))
    )
    (net (code "17") (name "/BA0") (class "Default")
      (node (ref "U1") (pin "79") (pinfunction "EMI_BA0_79") (pintype "output"))
      (node (ref "U2") (pin "26") (pinfunction "BA0_26") (pintype "input"))
    )
    (net (code "18") (name "/BA1") (class "Default")
      (node (ref "U1") (pin "80") (pinfunction "EMI_BA1_80") (pintype "output"))
      (node (ref "U2") (pin "27") (pinfunction "BA1_27") (pintype "input"))
    )
    (net (code "19") (name "/CASN") (class "Default")
      (node (ref "U1") (pin "61") (pinfunction "EMI_CASN_61") (pintype "output"))
      (node (ref "U2") (pin "22") (pinfunction "#CAS_22") (pintype "input"))
    )
    (net (code "20") (name "/CKE") (class "Default")
      (node (ref "U1") (pin "78") (pinfunction "EMI_CKE_78") (pintype "output"))
      (node (ref "U2") (pin "44") (pinfunction "CKE_44") (pintype "input"))
    )
    (net (code "21") (name "/CLK") (class "Default")
      (node (ref "R17") (pin "2") (pinfunction "2_2") (pintype "passive"))
      (node (ref "U1") (pin "36") (pinfunction "EMI_CLK_36") (pintype "output"))
      (node (ref "U2") (pin "45") (pinfunction "CK_45") (pintype "input"))
    )
    (net (code "22") (name "/CLKN") (class "Default")
      (node (ref "R17") (pin "1") (pinfunction "1_1") (pintype "passive"))
      (node (ref "U1") (pin "37") (pinfunction "EMI_CLKN_37") (pintype "output"))
      (node (ref "U2") (pin "46") (pinfunction "#CK_46") (pintype "input"))
    )
    (net (code "23") (name "/CS") (class "Default")
      (node (ref "R16") (pin "1") (pinfunction "1_1") (pintype "passive"))
      (node (ref "U1") (pin "63") (pinfunction "EMI_CE0N_63") (pintype "output"))
      (node (ref "U2") (pin "24") (pinfunction "#CS_24") (pintype "input"))
    )
    (net (code "24") (name "/D0") (class "Default")
      (node (ref "U1") (pin "41") (pinfunction "EMI_D00_41") (pintype "bidirectional"))
      (node (ref "U2") (pin "2") (pinfunction "DQ0_2") (pintype "bidirectional"))
    )
    (net (code "25") (name "/D1") (class "Default")
      (node (ref "U1") (pin "43") (pinfunction "EMI_D01_43") (pintype "bidirectional"))
      (node (ref "U2") (pin "4") (pinfunction "DQ1_4") (pintype "bidirectional"))
    )
    (net (code "26") (name "/D2") (class "Default")
      (node (ref "U1") (pin "42") (pinfunction "EMI_D02_42") (pintype "bidirectional"))
      (node (ref "U2") (pin "5") (pinfunction "DQ2_5") (pintype "bidirectional"))
    )
    (net (code "27") (name "/D3") (class "Default")
      (node (ref "U1") (pin "44") (pinfunction "EMI_D03_44") (pintype "bidirectional"))
      (node (ref "U2") (pin "7") (pinfunction "DQ3_7") (pintype "bidirectional"))
    )
    (net (code "28") (name "/D4") (class "Default")
      (node (ref "U1") (pin "47") (pinfunction "EMI_D04_47") (pintype "bidirectional"))
      (node (ref "U2") (pin "8") (pinfunction "DQ4_8") (pintype "bidirectional"))
    )
    (net (code "29") (name "/D5") (class "Default")
      (node (ref "U1") (pin "48") (pinfunction "EMI_D05_48") (pintype "bidirectional"))
      (node (ref "U2") (pin "10") (pinfunction "DQ5_10") (pintype "bidirectional"))
    )
    (net (code "30") (name "/D6") (class "Default")
      (node (ref "U1") (pin "49") (pinfunction "EMI_D06_49") (pintype "bidirectional"))
      (node (ref "U2") (pin "11") (pinfunction "DQ6_11") (pintype "bidirectional"))
    )
    (net (code "31") (name "/D7") (class "Default")
      (node (ref "U1") (pin "50") (pinfunction "EMI_D07_50") (pintype "bidirectional"))
      (node (ref "U2") (pin "13") (pinfunction "DQ7_13") (pintype "bidirectional"))
    )
    (net (code "32") (name "/D8") (class "Default")
      (node (ref "U1") (pin "51") (pinfunction "EMI_D08_51") (pintype "bidirectional"))
      (node (ref "U2") (pin "54") (pinfunction "DQ8_54") (pintype "bidirectional"))
    )
    (net (code "33") (name "/D9") (class "Default")
      (node (ref "U1") (pin "52") (pinfunction "EMI_D09_52") (pintype "bidirectional"))
      (node (ref "U2") (pin "56") (pinfunction "DQ9_56") (pintype "bidirectional"))
    )
    (net (code "34") (name "/D10") (class "Default")
      (node (ref "U1") (pin "54") (pinfunction "EMI_D10_54") (pintype "bidirectional"))
      (node (ref "U2") (pin "57") (pinfunction "DQ10_57") (pintype "bidirectional"))
    )
    (net (code "35") (name "/D11") (class "Default")
      (node (ref "U1") (pin "55") (pinfunction "EMI_D11_55") (pintype "bidirectional"))
      (node (ref "U2") (pin "59") (pinfunction "DQ11_59") (pintype "bidirectional"))
    )
    (net (code "36") (name "/D12") (class "Default")
      (node (ref "U1") (pin "57") (pinfunction "EMI_D12_57") (pintype "bidirectional"))
      (node (ref "U2") (pin "60") (pinfunction "DQ12_60") (pintype "bidirectional"))
    )
    (net (code "37") (name "/D13") (class "Default")
      (node (ref "U1") (pin "58") (pinfunction "EMI_D13_58") (pintype "bidirectional"))
      (node (ref "U2") (pin "62") (pinfunction "DQ13_62") (pintype "bidirectional"))
    )
    (net (code "38") (name "/D14") (class "Default")
      (node (ref "U1") (pin "60") (pinfunction "EMI_D14_60") (pintype "bidirectional"))
      (node (ref "U2") (pin "63") (pinfunction "DQ14_63") (pintype "bidirectional"))
    )
    (net (code "39") (name "/D15") (class "Default")
      (node (ref "U1") (pin "59") (pinfunction "EMI_D15_59") (pintype "bidirectional"))
      (node (ref "U2") (pin "65") (pinfunction "DQ15_65") (pintype "bidirectional"))
    )
    (net (code "40") (name "/DCDC_VDDA") (class "Default")
      (node (ref "C17") (pin "2") (pinfunction "2_2") (pintype "passive"))
      (node (ref "C18") (pin "2") (pinfunction "2_2") (pintype "passive"))
      (node (ref "C25") (pin "2") (pinfunction "2_2") (pintype "passive"))
      (node (ref "U1") (pin "110") (pinfunction "VDDA1_110") (pintype "power_in"))
      (node (ref "U1") (pin "96") (pinfunction "DCDC_VDDA_96") (pintype "power_in"))
    )
    (net (code "41") (name "/DCDC_VDDD") (class "Default")
      (node (ref "C1") (pin "2") (pinfunction "2_2") (pintype "passive"))
      (node (ref "C13") (pin "2") (pinfunction "2_2") (pintype "passive"))
      (node (ref "C14") (pin "2") (pinfunction "2_2") (pintype "passive"))
      (node (ref "C2") (pin "2") (pinfunction "2_2") (pintype "passive"))
      (node (ref "U1") (pin "1") (pinfunction "VDDD1_1") (pintype "power_in"))
      (node (ref "U1") (pin "93") (pinfunction "VDDD3_93") (pintype "power_in"))
      (node (ref "U1") (pin "94") (pinfunction "DCDC_VDDD_94") (pintype "power_in"))
    )
    (net (code "42") (name "/DEBUG") (class "Default")
      (node (ref "SJTAG135") (pin "4") (pinfunction "4_4") (pintype "passive"))
      (node (ref "U1") (pin "89") (pinfunction "DEBUG_89") (pintype "bidirectional"))
      (node (ref "U_DEBUG135") (pin "4") (pinfunction "4_4") (pintype "passive"))
    )
    (net (code "43") (name "/DQM0") (class "Default")
      (node (ref "U1") (pin "46") (pinfunction "EMI_DQM0_46") (pintype "output"))
      (node (ref "U2") (pin "20") (pinfunction "LDM_20") (pintype "input"))
    )
    (net (code "44") (name "/DQM1") (class "Default")
      (node (ref "U1") (pin "56") (pinfunction "EMI_DQM1_56") (pintype "output"))
      (node (ref "U2") (pin "47") (pinfunction "UDM_47") (pintype "input"))
    )
    (net (code "45") (name "/DQS0") (class "Default")
      (node (ref "U1") (pin "39") (pinfunction "EMI_DQS0_39") (pintype "output"))
      (node (ref "U2") (pin "16") (pinfunction "LDQS_16") (pintype "bidirectional"))
    )
    (net (code "46") (name "/DQS1") (class "Default")
      (node (ref "U1") (pin "40") (pinfunction "EMI_DQS1_40") (pintype "output"))
      (node (ref "U2") (pin "51") (pinfunction "UDQS_51") (pintype "input"))
    )
    (net (code "47") (name "/I2C_SCL") (class "Default")
      (node (ref "R11") (pin "1") (pinfunction "1_1") (pintype "passive"))
      (node (ref "SCL_SW/SCL_HW135") (pin "2") (pinfunction "2_2") (pintype "passive"))
      (node (ref "UEXT135") (pin "5") (pinfunction "5_5") (pintype "passive"))
    )
    (net (code "48") (name "/I2C_SDA") (class "Default")
      (node (ref "R12") (pin "1") (pinfunction "1_1") (pintype "passive"))
      (node (ref "SDA_SW/SDA_HW135") (pin "2") (pinfunction "2_2") (pintype "passive"))
      (node (ref "UEXT135") (pin "6") (pinfunction "6_6") (pintype "passive"))
    )
    (net (code "49") (name "/LED1") (class "Default")
      (node (ref "LED1") (pin "A") (pinfunction "A_A") (pintype "passive"))
      (node (ref "U1") (pin "88") (pinfunction "SSP1_DETECT/GPMI_CE3N/USB_ID_88") (pintype "bidirectional"))
    )
    (net (code "50") (name "/PIN1{slash}LCD_D00") (class "Default")
      (node (ref "GPIO_CON135") (pin "35") (pinfunction "35_35") (pintype "passive"))
      (node (ref "RM2") (pin "4.2") (pinfunction "4.2_4.2") (pintype "passive"))
      (node (ref "RM3") (pin "4.1") (pinfunction "4.1_4.1") (pintype "passive"))
      (node (ref "U1") (pin "2") (pinfunction "LCD_D00_2") (pintype "bidirectional"))
    )
    (net (code "51") (name "/PIN2{slash}LCD_D01") (class "Default")
      (node (ref "GPIO_CON135") (pin "33") (pinfunction "33_33") (pintype "passive"))
      (node (ref "RM2") (pin "3.2") (pinfunction "3.2_3.2") (pintype "passive"))
      (node (ref "RM3") (pin "3.1") (pinfunction "3.1_3.1") (pintype "passive"))
      (node (ref "U1") (pin "3") (pinfunction "LCD_D01_3") (pintype "bidirectional"))
    )
    (net (code "52") (name "/PIN3{slash}LCD_D02") (class "Default")
      (node (ref "GPIO_CON135") (pin "31") (pinfunction "31_31") (pintype "passive"))
      (node (ref "RM2") (pin "2.2") (pinfunction "2.2_2.2") (pintype "passive"))
      (node (ref "RM3") (pin "2.1") (pinfunction "2.1_2.1") (pintype "passive"))
      (node (ref "U1") (pin "4") (pinfunction "LCD_D02_4") (pintype "bidirectional"))
    )
    (net (code "53") (name "/PIN4{slash}LCD_D03") (class "Default")
      (node (ref "GPIO_CON135") (pin "29") (pinfunction "29_29") (pintype "passive"))
      (node (ref "RM2") (pin "1.2") (pinfunction "1.2_1.2") (pintype "passive"))
      (node (ref "RM3") (pin "1.1") (pinfunction "1.1_1.1") (pintype "passive"))
      (node (ref "U1") (pin "5") (pinfunction "LCD_D03_5") (pintype "bidirectional"))
    )
    (net (code "54") (name "/PIN5{slash}LCD_D04") (class "Default")
      (node (ref "GPIO_CON135") (pin "27") (pinfunction "27_27") (pintype "passive"))
      (node (ref "U1") (pin "6") (pinfunction "LCD_D04_6") (pintype "bidirectional"))
    )
    (net (code "55") (name "/PIN6{slash}LCD_D05") (class "Default")
      (node (ref "GPIO_CON135") (pin "25") (pinfunction "25_25") (pintype "passive"))
      (node (ref "R14") (pin "2") (pinfunction "2_2") (pintype "passive"))
      (node (ref "U1") (pin "7") (pinfunction "LCD_D05_7") (pintype "bidirectional"))
    )
    (net (code "56") (name "/PIN7{slash}LCD_D06") (class "Default")
      (node (ref "GPIO_CON135") (pin "23") (pinfunction "23_23") (pintype "passive"))
      (node (ref "U1") (pin "8") (pinfunction "LCD_D06_8") (pintype "bidirectional"))
    )
    (net (code "57") (name "/PIN8{slash}LCD_D07") (class "Default")
      (node (ref "GPIO_CON135") (pin "21") (pinfunction "21_21") (pintype "passive"))
      (node (ref "U1") (pin "9") (pinfunction "LCD_D07_9") (pintype "bidirectional"))
    )
    (net (code "58") (name "/PIN9{slash}LCD_D08{slash}SSP2_MISO") (class "Default")
      (node (ref "GPIO_CON135") (pin "19") (pinfunction "19_19") (pintype "passive"))
      (node (ref "U1") (pin "22") (pinfunction "GPMI_D00/LCD_D08/SSP2_DATA0_22") (pintype "bidirectional"))
      (node (ref "UEXT135") (pin "7") (pinfunction "7_7") (pintype "passive"))
    )
    (net (code "59") (name "/PIN10{slash}LCD_D09") (class "Default")
      (node (ref "GPIO_CON135") (pin "17") (pinfunction "17_17") (pintype "passive"))
      (node (ref "U1") (pin "23") (pinfunction "GPMI_D01/LCD_D09/SSP2_DATA1_23") (pintype "bidirectional"))
    )
    (net (code "60") (name "/PIN11{slash}LCD_D10") (class "Default")
      (node (ref "GPIO_CON135") (pin "15") (pinfunction "15_15") (pintype "passive"))
      (node (ref "U1") (pin "24") (pinfunction "GPMI_D02/LCD_D10/SSP2_DATA2_24") (pintype "bidirectional"))
    )
    (net (code "61") (name "/PIN12{slash}LCD_D11{slash}UEXT_CS") (class "Default")
      (node (ref "GPIO_CON135") (pin "13") (pinfunction "13_13") (pintype "passive"))
      (node (ref "R13") (pin "1") (pinfunction "1_1") (pintype "passive"))
      (node (ref "U1") (pin "25") (pinfunction "GPMI_D03/LCD_D11/SSP2_DATA3_25") (pintype "bidirectional"))
      (node (ref "UEXT135") (pin "10") (pinfunction "10_10") (pintype "passive"))
    )
    (net (code "62") (name "/PIN13{slash}LCD_D12") (class "Default")
      (node (ref "GPIO_CON135") (pin "11") (pinfunction "11_11") (pintype "passive"))
      (node (ref "U1") (pin "27") (pinfunction "GPMI_D04/LCD_D12/SSP2_DATA4_27") (pintype "bidirectional"))
    )
    (net (code "63") (name "/PIN14{slash}LCD_D13") (class "Default")
      (node (ref "GPIO_CON135") (pin "9") (pinfunction "9_9") (pintype "passive"))
      (node (ref "U1") (pin "26") (pinfunction "GPMI_D05/LCD_D13/SSP2_DATA5_26") (pintype "bidirectional"))
    )
    (net (code "64") (name "/PIN15{slash}LCD_D14") (class "Default")
      (node (ref "GPIO_CON135") (pin "7") (pinfunction "7_7") (pintype "passive"))
      (node (ref "U1") (pin "29") (pinfunction "GPMI_D06/LCD_D14/SSP2_DATA6_29") (pintype "bidirectional"))
    )
    (net (code "65") (name "/PIN16{slash}LCD_D15") (class "Default")
      (node (ref "GPIO_CON135") (pin "5") (pinfunction "5_5") (pintype "passive"))
      (node (ref "U1") (pin "28") (pinfunction "GPMI_D07/LCD_D15/SSP2_DATA7_28") (pintype "bidirectional"))
    )
    (net (code "66") (name "/PIN17{slash}LCD_D16") (class "Default")
      (node (ref "GPIO_CON135") (pin "3") (pinfunction "3_3") (pintype "passive"))
      (node (ref "U1") (pin "19") (pinfunction "GPMI_CLE/LCD_D16_19") (pintype "bidirectional"))
    )
    (net (code "67") (name "/PIN18{slash}LCD_D17{slash}USB_EN") (class "Default")
      (node (ref "GPIO_CON135") (pin "4") (pinfunction "4_4") (pintype "passive"))
      (node (ref "R28") (pin "2") (pinfunction "2_2") (pintype "passive"))
      (node (ref "U1") (pin "20") (pinfunction "GPMI_ALE/LCD_D17_20") (pintype "bidirectional"))
      (node (ref "U3") (pin "4") (pinfunction "EN_4") (pintype "bidirectional"))
    )
    (net (code "68") (name "/PIN19{slash}LCD_DOTCLK") (class "Default")
      (node (ref "GPIO_CON135") (pin "6") (pinfunction "6_6") (pintype "passive"))
      (node (ref "U1") (pin "17") (pinfunction "LCD_DOTCK/GPMI_RDY3_17") (pintype "bidirectional"))
    )
    (net (code "69") (name "/PIN20{slash}LCD_VSYNC") (class "Default")
      (node (ref "GPIO_CON135") (pin "8") (pinfunction "8_8") (pintype "passive"))
      (node (ref "U1") (pin "16") (pinfunction "LCD_VSYNC/LCD_BUSY_16") (pintype "bidirectional"))
    )
    (net (code "70") (name "/PIN21{slash}LCD_HSYNC{slash}I2C_SDA") (class "Default")
      (node (ref "GPIO_CON135") (pin "10") (pinfunction "10_10") (pintype "passive"))
      (node (ref "SDA_SW/SDA_HW135") (pin "1") (pinfunction "1_1") (pintype "passive"))
      (node (ref "U1") (pin "15") (pinfunction "LCD_HSYNC/I2C_SDA_15") (pintype "bidirectional"))
    )
    (net (code "71") (name "/PIN22{slash}LCD_EN{slash}I2C_SCL") (class "Default")
      (node (ref "GPIO_CON135") (pin "12") (pinfunction "12_12") (pintype "passive"))
      (node (ref "SCL_SW/SCL_HW135") (pin "1") (pinfunction "1_1") (pintype "passive"))
      (node (ref "U1") (pin "11") (pinfunction "LCD_ENABLE/I2C_SCL_11") (pintype "bidirectional"))
    )
    (net (code "72") (name "/PIN23{slash}LCD_DISP") (class "Default")
      (node (ref "GPIO_CON135") (pin "14") (pinfunction "14_14") (pintype "passive"))
      (node (ref "U1") (pin "12") (pinfunction "LCD_RESET/GPMI_CE3N_12") (pintype "bidirectional"))
    )
    (net (code "73") (name "/PIN24{slash}LCD_WR") (class "Default")
      (node (ref "GPIO_CON135") (pin "16") (pinfunction "16_16") (pintype "passive"))
      (node (ref "U1") (pin "13") (pinfunction "LCD_WR_13") (pintype "bidirectional"))
    )
    (net (code "74") (name "/PIN25{slash}LCD_RS") (class "Default")
      (node (ref "GPIO_CON135") (pin "18") (pinfunction "18_18") (pintype "passive"))
      (node (ref "R15") (pin "2") (pinfunction "2_2") (pintype "passive"))
      (node (ref "U1") (pin "14") (pinfunction "LCD_RS_14") (pintype "bidirectional"))
    )
    (net (code "75") (name "/PIN26{slash}LCD_CS") (class "Default")
      (node (ref "GPIO_CON135") (pin "20") (pinfunction "20_20") (pintype "passive"))
      (node (ref "U1") (pin "10") (pinfunction "LCD_CS_10") (pintype "bidirectional"))
    )
    (net (code "76") (name "/PIN27{slash}PWM2") (class "Default")
      (node (ref "GPIO_CON135") (pin "22") (pinfunction "22_22") (pintype "passive"))
      (node (ref "U1") (pin "91") (pinfunction "PWM2/GPMI_RDY3_91") (pintype "bidirectional"))
    )
    (net (code "77") (name "/PIN28{slash}SOFT_SDA") (class "Default")
      (node (ref "GPIO_CON135") (pin "24") (pinfunction "24_24") (pintype "passive"))
      (node (ref "SDA_SW/SDA_HW135") (pin "3") (pinfunction "3_3") (pintype "passive"))
      (node (ref "U1") (pin "31") (pinfunction "GPMI_RDN_31") (pintype "bidirectional"))
    )
    (net (code "78") (name "/PIN29{slash}SOFT_SCL") (class "Default")
      (node (ref "GPIO_CON135") (pin "26") (pinfunction "26_26") (pintype "passive"))
      (node (ref "SCL_SW/SCL_HW135") (pin "3") (pinfunction "3_3") (pintype "passive"))
      (node (ref "U1") (pin "34") (pinfunction "GPMI_WPN_34") (pintype "bidirectional"))
    )
    (net (code "79") (name "/PIN30") (class "Default")
      (node (ref "GPIO_CON135") (pin "28") (pinfunction "28_28") (pintype "passive"))
      (node (ref "U1") (pin "81") (pinfunction "GPMI_CE1N_81") (pintype "bidirectional"))
    )
    (net (code "80") (name "/PIN31") (class "Default")
      (node (ref "GPIO_CON135") (pin "30") (pinfunction "30_30") (pintype "passive"))
      (node (ref "U1") (pin "82") (pinfunction "GPMI_CE0N_82") (pintype "bidirectional"))
    )
    (net (code "81") (name "/PIN32{slash}LRADC1") (class "Default")
      (node (ref "GPIO_CON135") (pin "32") (pinfunction "32_32") (pintype "passive"))
      (node (ref "U1") (pin "107") (pinfunction "LRADC1_107") (pintype "bidirectional"))
    )
    (net (code "82") (name "/PIN33{slash}LRADC0") (class "Default")
      (node (ref "GPIO_CON135") (pin "34") (pinfunction "34_34") (pintype "passive"))
      (node (ref "U1") (pin "108") (pinfunction "LRADC0_108") (pintype "bidirectional"))
    )
    (net (code "83") (name "/PIN34{slash}MIC") (class "Default")
      (node (ref "GPIO_CON135") (pin "36") (pinfunction "36_36") (pintype "passive"))
      (node (ref "U1") (pin "116") (pinfunction "MIC_116") (pintype "input"))
    )
    (net (code "84") (name "/PSWITCH") (class "Default")
      (node (ref "R23") (pin "1") (pinfunction "1_1") (pintype "passive"))
      (node (ref "U1") (pin "119") (pinfunction "PSWITCH_119") (pintype "input"))
    )
    (net (code "85") (name "/PWM0{slash}DUART_RXD") (class "Default")
      (node (ref "R9") (pin "1") (pinfunction "1_1") (pintype "passive"))
      (node (ref "U1") (pin "125") (pinfunction "PWM0/ROTARYA/DUART_RX_125") (pintype "bidirectional"))
      (node (ref "U_DEBUG135") (pin "1") (pinfunction "1_1") (pintype "passive"))
    )
    (net (code "86") (name "/PWM1{slash}DUART_TXD") (class "Default")
      (node (ref "U1") (pin "126") (pinfunction "PWM1/ROTARYB/DUART_TX_126") (pintype "bidirectional"))
      (node (ref "U_DEBUG135") (pin "2") (pinfunction "2_2") (pintype "passive"))
    )
    (net (code "87") (name "/RASN") (class "Default")
      (node (ref "U1") (pin "62") (pinfunction "EMI_RASN_62") (pintype "output"))
      (node (ref "U2") (pin "23") (pinfunction "#RAS_23") (pintype "input"))
    )
    (net (code "88") (name "/RESET") (class "Default")
      (node (ref "R42") (pin "2") (pinfunction "2_2") (pintype "passive"))
      (node (ref "RESET135") (pin "2") (pinfunction "S_2") (pintype "passive"))
    )
    (net (code "89") (name "/SD_VCC") (class "Default")
      (node (ref "C29") (pin "2") (pinfunction "2_2") (pintype "passive"))
      (node (ref "C71") (pin "2") (pinfunction "2_2") (pintype "passive"))
      (node (ref "JTAG135") (pin "5") (pinfunction "5_5") (pintype "passive"))
      (node (ref "L6") (pin "2") (pinfunction "2_2") (pintype "passive"))
      (node (ref "SD135") (pin "4") (pinfunction "VDD_4") (pintype "power_in"))
    )
    (net (code "90") (name "/SJTAG_PSW") (class "Default")
      (node (ref "PWR_BUT135") (pin "1") (pinfunction "P_1") (pintype "passive"))
      (node (ref "R23") (pin "2") (pinfunction "2_2") (pintype "passive"))
      (node (ref "R24") (pin "2") (pinfunction "2_2") (pintype "passive"))
      (node (ref "REC135") (pin "2") (pinfunction "2_2") (pintype "passive"))
      (node (ref "RM1") (pin "1.2") (pinfunction "2_1.2") (pintype "passive"))
      (node (ref "SJTAG135") (pin "3") (pinfunction "3_3") (pintype "passive"))
    )
    (net (code "91") (name "/SSP1_CMD") (class "Default")
      (node (ref "JTAG135") (pin "6") (pinfunction "6_6") (pintype "passive"))
      (node (ref "R21") (pin "1") (pinfunction "1_1") (pintype "passive"))
      (node (ref "SD135") (pin "3") (pinfunction "CMD/DI_3") (pintype "input"))
      (node (ref "U1") (pin "83") (pinfunction "SSP1_CMD/SPI1_MOSI/JTAG_TDO_83") (pintype "bidirectional"))
    )
    (net (code "92") (name "/SSP1_DATA0") (class "Default")
      (node (ref "JTAG135") (pin "2") (pinfunction "2_2") (pintype "passive"))
      (node (ref "RM1") (pin "3.1") (pinfunction "1_3.1") (pintype "passive"))
      (node (ref "SD135") (pin "7") (pinfunction "DAT0/DO_7") (pintype "output"))
      (node (ref "U1") (pin "84") (pinfunction "SSP1_DATA0/SPI1_MISO/JTAG_TDI_84") (pintype "bidirectional"))
    )
    (net (code "93") (name "/SSP1_DATA1") (class "Default")
      (node (ref "JTAG135") (pin "1") (pinfunction "1_1") (pintype "passive"))
      (node (ref "RM1") (pin "2.1") (pinfunction "1_2.1") (pintype "passive"))
      (node (ref "SD135") (pin "8") (pinfunction "DAT1/RES_8") (pintype "bidirectional"))
      (node (ref "U1") (pin "85") (pinfunction "SSP1_DATA1/I2C_SCL/JTAG_TCLK_85") (pintype "bidirectional"))
    )
    (net (code "94") (name "/SSP1_DATA2") (class "Default")
      (node (ref "JTAG135") (pin "8") (pinfunction "8_8") (pintype "passive"))
      (node (ref "RM1") (pin "4.1") (pinfunction "1_4.1") (pintype "passive"))
      (node (ref "SD135") (pin "1") (pinfunction "DAT2/RES_1") (pintype "bidirectional"))
      (node (ref "U1") (pin "86") (pinfunction "SSP1_DATA2/I2C_SDA/JTAG_RTCK_86") (pintype "bidirectional"))
    )
    (net (code "95") (name "/SSP1_DATA3") (class "Default")
      (node (ref "JTAG135") (pin "7") (pinfunction "7_7") (pintype "passive"))
      (node (ref "R20") (pin "1") (pinfunction "1_1") (pintype "passive"))
      (node (ref "SD135") (pin "2") (pinfunction "CD/DAT3/CS_2") (pintype "input"))
      (node (ref "U1") (pin "87") (pinfunction "SSP1_DATA3/SPI1_SS#/JTAG_TMS_87") (pintype "bidirectional"))
    )
    (net (code "96") (name "/SSP1_SCK") (class "Default")
      (node (ref "JTAG135") (pin "4") (pinfunction "4_4") (pintype "passive"))
      (node (ref "SD135") (pin "5") (pinfunction "CLK/SCLK_5") (pintype "input"))
      (node (ref "U1") (pin "90") (pinfunction "SSP1_SCK/SPI1_SCK/JTAG_TRST_90") (pintype "bidirectional"))
    )
    (net (code "97") (name "/SSP2_MOSI") (class "Default")
      (node (ref "U1") (pin "21") (pinfunction "GPMI_RDY1/SSP2_CMD_21") (pintype "bidirectional"))
      (node (ref "UEXT135") (pin "8") (pinfunction "8_8") (pintype "passive"))
    )
    (net (code "98") (name "/SSP2_SCK") (class "Default")
      (node (ref "U1") (pin "33") (pinfunction "GPMI_WRN/SSP2_SCK_33") (pintype "bidirectional"))
      (node (ref "UEXT135") (pin "9") (pinfunction "9_9") (pintype "passive"))
    )
    (net (code "99") (name "/TEST_PAD") (class "Default")
      (node (ref "T_P135") (pin "P$1") (pinfunction "PP_P$1") (pintype "passive"))
      (node (ref "U1") (pin "32") (pinfunction "GPMI_RDY0/SSP2_DETECT_32") (pintype "bidirectional"))
    )
    (net (code "100") (name "/USB_DM") (class "Default")
      (node (ref "PGM_FUSES135") (pin "1") (pinfunction "1_1") (pintype "passive"))
      (node (ref "U1") (pin "123") (pinfunction "USB_DM_123") (pintype "bidirectional"))
      (node (ref "U4") (pin "25") (pinfunction "DM0_25") (pintype "bidirectional"))
    )
    (net (code "101") (name "/USB_DP") (class "Default")
      (node (ref "PGM_FUSES135") (pin "2") (pinfunction "2_2") (pintype "passive"))
      (node (ref "U1") (pin "124") (pinfunction "USB_DP_124") (pintype "bidirectional"))
      (node (ref "U4") (pin "26") (pinfunction "DP0_26") (pintype "bidirectional"))
    )
    (net (code "102") (name "/VDDXTAL") (class "Default")
      (node (ref "C8") (pin "2") (pinfunction "2_2") (pintype "passive"))
      (node (ref "PWR_BUT135") (pin "2") (pinfunction "S_2") (pintype "passive"))
      (node (ref "U1") (pin "120") (pinfunction "VDDXTAL_120") (pintype "passive"))
    )
    (net (code "103") (name "/WEN") (class "Default")
      (node (ref "U1") (pin "77") (pinfunction "EMI_WEN_77") (pintype "output"))
      (node (ref "U2") (pin "21") (pinfunction "#WE_21") (pintype "input"))
    )
    (net (code "104") (name "/X1") (class "Default")
      (node (ref "C42") (pin "2") (pinfunction "2_2") (pintype "passive"))
      (node (ref "Q2") (pin "2") (pinfunction "2_2") (pintype "passive"))
      (node (ref "U4") (pin "6") (pinfunction "X1_6") (pintype "input"))
    )
    (net (code "105") (name "/X2") (class "Default")
      (node (ref "C43") (pin "2") (pinfunction "2_2") (pintype "passive"))
      (node (ref "Q2") (pin "1") (pinfunction "1_1") (pintype "passive"))
      (node (ref "U4") (pin "7") (pinfunction "X2_7") (pintype "output"))
    )
    (net (code "106") (name "/XTALI") (class "Default")
      (node (ref "C23") (pin "2") (pinfunction "2_2") (pintype "passive"))
      (node (ref "Q1") (pin "2") (pinfunction "2_2") (pintype "passive"))
      (node (ref "T2") (pin "3") (pinfunction "C_3") (pintype "passive"))
      (node (ref "U1") (pin "122") (pinfunction "XTALI_122") (pintype "input"))
    )
    (net (code "107") (name "/XTALO") (class "Default")
      (node (ref "C24") (pin "2") (pinfunction "2_2") (pintype "passive"))
      (node (ref "Q1") (pin "1") (pinfunction "1_1") (pintype "passive"))
      (node (ref "T1") (pin "3") (pinfunction "C_3") (pintype "passive"))
      (node (ref "U1") (pin "121") (pinfunction "XTALO_121") (pintype "output"))
    )
    (net (code "108") (name "2.5V") (class "Default")
      (node (ref "C22") (pin "2") (pinfunction "2_2") (pintype "passive"))
      (node (ref "C30") (pin "2") (pinfunction "2_2") (pintype "passive"))
      (node (ref "C31") (pin "2") (pinfunction "2_2") (pintype "passive"))
      (node (ref "C32") (pin "2") (pinfunction "2_2") (pintype "passive"))
      (node (ref "C33") (pin "2") (pinfunction "2_2") (pintype "passive"))
      (node (ref "C34") (pin "2") (pinfunction "2_2") (pintype "passive"))
      (node (ref "C35") (pin "2") (pinfunction "2_2") (pintype "passive"))
      (node (ref "C36") (pin "2") (pinfunction "2_2") (pintype "passive"))
      (node (ref "C37") (pin "2") (pinfunction "2_2") (pintype "passive"))
      (node (ref "C38") (pin "1") (pinfunction "1_1") (pintype "passive"))
      (node (ref "C5") (pin "2") (pinfunction "2_2") (pintype "passive"))
      (node (ref "C6") (pin "2") (pinfunction "2_2") (pintype "passive"))
      (node (ref "C7") (pin "2") (pinfunction "2_2") (pintype "passive"))
      (node (ref "R16") (pin "2") (pinfunction "2_2") (pintype "passive"))
      (node (ref "R18") (pin "2") (pinfunction "2_2") (pintype "passive"))
      (node (ref "U1") (pin "106") (pinfunction "VDDM/LRADC4_106") (pintype "power_in"))
      (node (ref "U1") (pin "38") (pinfunction "VDDIO_EMIQ_38") (pintype "power_in"))
      (node (ref "U1") (pin "45") (pinfunction "VDDIO_EMI1_45") (pintype "power_in"))
      (node (ref "U1") (pin "53") (pinfunction "VDDIO_EMI2_53") (pintype "power_in"))
      (node (ref "U2") (pin "1") (pinfunction "VDD1_1") (pintype "power_in"))
      (node (ref "U2") (pin "15") (pinfunction "VDDQ3_15") (pintype "power_in"))
      (node (ref "U2") (pin "18") (pinfunction "VDD2_18") (pintype "power_in"))
      (node (ref "U2") (pin "3") (pinfunction "VDDQ1_3") (pintype "power_in"))
      (node (ref "U2") (pin "33") (pinfunction "VDD3_33") (pintype "power_in"))
      (node (ref "U2") (pin "55") (pinfunction "VDDQ4_55") (pintype "power_in"))
      (node (ref "U2") (pin "61") (pinfunction "VDDQ5_61") (pintype "power_in"))
      (node (ref "U2") (pin "9") (pinfunction "VDDQ2_9") (pintype "power_in"))
    )
    (net (code "109") (name "3.3VIO") (class "Default")
      (node (ref "3.3VIO_E135") (pin "2") (pinfunction "2_2") (pintype "passive"))
      (node (ref "C15") (pin "2") (pinfunction "2_2") (pintype "passive"))
      (node (ref "C16") (pin "2") (pinfunction "2_2") (pintype "passive"))
      (node (ref "C3") (pin "2") (pinfunction "2_2") (pintype "passive"))
      (node (ref "C4") (pin "2") (pinfunction "2_2") (pintype "passive"))
      (node (ref "C60") (pin "1") (pinfunction "1_1") (pintype "passive"))
      (node (ref "D00_H135") (pin "2") (pinfunction "2_2") (pintype "passive"))
      (node (ref "D01_H135") (pin "2") (pinfunction "2_2") (pintype "passive"))
      (node (ref "D02_H135") (pin "2") (pinfunction "2_2") (pintype "passive"))
      (node (ref "D03_H135") (pin "2") (pinfunction "2_2") (pintype "passive"))
      (node (ref "D2") (pin "2") (pinfunction "K_2") (pintype "passive"))
      (node (ref "L6") (pin "1") (pinfunction "1_1") (pintype "passive"))
      (node (ref "PWR_SEL135") (pin "1") (pinfunction "1_1") (pintype "passive"))
      (node (ref "R15") (pin "1") (pinfunction "1_1") (pintype "passive"))
      (node (ref "R21") (pin "2") (pinfunction "2_2") (pintype "passive"))
      (node (ref "R25") (pin "2") (pinfunction "2_2") (pintype "passive"))
      (node (ref "R9") (pin "2") (pinfunction "2_2") (pintype "passive"))
      (node (ref "RESET135") (pin "1") (pinfunction "P_1") (pintype "passive"))
      (node (ref "RM1") (pin "2.2") (pinfunction "2_2.2") (pintype "passive"))
      (node (ref "RM1") (pin "3.2") (pinfunction "2_3.2") (pintype "passive"))
      (node (ref "RM1") (pin "4.2") (pinfunction "2_4.2") (pintype "passive"))
      (node (ref "U1") (pin "18") (pinfunction "VDDIO33_1_18") (pintype "power_in"))
      (node (ref "U1") (pin "92") (pinfunction "VDDIO33_3_92") (pintype "power_in"))
      (node (ref "U1") (pin "95") (pinfunction "DCDC_VDDIO_95") (pintype "power_in"))
    )
    (net (code "110") (name "3.3VREG") (class "Default")
      (node (ref "3.3VIO_E135") (pin "1") (pinfunction "1_1") (pintype "passive"))
      (node (ref "3.3V_E135") (pin "2") (pinfunction "2_2") (pintype "passive"))
      (node (ref "C65") (pin "1") (pinfunction "1_1") (pintype "passive"))
      (node (ref "GPIO_CON135") (pin "38") (pinfunction "38_38") (pintype "passive"))
      (node (ref "PWR_SEL135") (pin "3") (pinfunction "3_3") (pintype "passive"))
      (node (ref "R11") (pin "2") (pinfunction "2_2") (pintype "passive"))
      (node (ref "R12") (pin "2") (pinfunction "2_2") (pintype "passive"))
      (node (ref "R13") (pin "2") (pinfunction "2_2") (pintype "passive"))
      (node (ref "SJTAG135") (pin "1") (pinfunction "1_1") (pintype "passive"))
      (node (ref "UEXT135") (pin "1") (pinfunction "1_1") (pintype "passive"))
    )
    (net (code "111") (name "BAT") (class "Default")
      (node (ref "C19") (pin "2") (pinfunction "2_2") (pintype "passive"))
      (node (ref "C20") (pin "2") (pinfunction "2_2") (pintype "passive"))
      (node (ref "C21") (pin "2") (pinfunction "2_2") (pintype "passive"))
      (node (ref "C67") (pin "2") (pinfunction "2_2") (pintype "passive"))
      (node (ref "D1") (pin "A") (pinfunction "A_A") (pintype "passive"))
      (node (ref "GPIO_CON135") (pin "1") (pinfunction "1_1") (pintype "passive"))
      (node (ref "LIPO_BAT135") (pin "1") (pinfunction "1_1") (pintype "passive"))
      (node (ref "U1") (pin "100") (pinfunction "DCDC_BATTERY_100") (pintype "power_in"))
      (node (ref "U1") (pin "103") (pinfunction "BATT_103") (pintype "input"))
    )
    (net (code "112") (name "GND") (class "Default")
      (node (ref "C1") (pin "1") (pinfunction "1_1") (pintype "passive"))
      (node (ref "C10") (pin "1") (pinfunction "1_1") (pintype "passive"))
      (node (ref "C11") (pin "1") (pinfunction "1_1") (pintype "passive"))
      (node (ref "C12") (pin "1") (pinfunction "1_1") (pintype "passive"))
      (node (ref "C13") (pin "1") (pinfunction "1_1") (pintype "passive"))
      (node (ref "C14") (pin "1") (pinfunction "1_1") (pintype "passive"))
      (node (ref "C15") (pin "1") (pinfunction "1_1") (pintype "passive"))
      (node (ref "C16") (pin "1") (pinfunction "1_1") (pintype "passive"))
      (node (ref "C17") (pin "1") (pinfunction "1_1") (pintype "passive"))
      (node (ref "C18") (pin "1") (pinfunction "1_1") (pintype "passive"))
      (node (ref "C19") (pin "1") (pinfunction "1_1") (pintype "passive"))
      (node (ref "C2") (pin "1") (pinfunction "1_1") (pintype "passive"))
      (node (ref "C20") (pin "1") (pinfunction "1_1") (pintype "passive"))
      (node (ref "C21") (pin "1") (pinfunction "1_1") (pintype "passive"))
      (node (ref "C22") (pin "1") (pinfunction "1_1") (pintype "passive"))
      (node (ref "C23") (pin "1") (pinfunction "1_1") (pintype "passive"))
      (node (ref "C24") (pin "1") (pinfunction "1_1") (pintype "passive"))
      (node (ref "C25") (pin "1") (pinfunction "1_1") (pintype "passive"))
      (node (ref "C26") (pin "1") (pinfunction "1_1") (pintype "passive"))
      (node (ref "C29") (pin "1") (pinfunction "1_1") (pintype "passive"))
      (node (ref "C3") (pin "1") (pinfunction "1_1") (pintype "passive"))
      (node (ref "C30") (pin "1") (pinfunction "1_1") (pintype "passive"))
      (node (ref "C31") (pin "1") (pinfunction "1_1") (pintype "passive"))
      (node (ref "C32") (pin "1") (pinfunction "1_1") (pintype "passive"))
      (node (ref "C33") (pin "1") (pinfunction "1_1") (pintype "passive"))
      (node (ref "C34") (pin "1") (pinfunction "1_1") (pintype "passive"))
      (node (ref "C35") (pin "1") (pinfunction "1_1") (pintype "passive"))
      (node (ref "C36") (pin "1") (pinfunction "1_1") (pintype "passive"))
      (node (ref "C37") (pin "1") (pinfunction "1_1") (pintype "passive"))
      (node (ref "C39") (pin "1") (pinfunction "1_1") (pintype "passive"))
      (node (ref "C4") (pin "1") (pinfunction "1_1") (pintype "passive"))
      (node (ref "C40") (pin "2") (pinfunction "2_2") (pintype "passive"))
      (node (ref "C41") (pin "2") (pinfunction "2_2") (pintype "passive"))
      (node (ref "C42") (pin "1") (pinfunction "1_1") (pintype "passive"))
      (node (ref "C43") (pin "1") (pinfunction "1_1") (pintype "passive"))
      (node (ref "C44") (pin "2") (pinfunction "2_2") (pintype "passive"))
      (node (ref "C45") (pin "2") (pinfunction "2_2") (pintype "passive"))
      (node (ref "C46") (pin "2") (pinfunction "2_2") (pintype "passive"))
      (node (ref "C47") (pin "2") (pinfunction "2_2") (pintype "passive"))
      (node (ref "C48") (pin "-") (pinfunction "-_-") (pintype "passive"))
      (node (ref "C49") (pin "2") (pinfunction "2_2") (pintype "passive"))
      (node (ref "C5") (pin "1") (pinfunction "1_1") (pintype "passive"))
      (node (ref "C50") (pin "2") (pinfunction "2_2") (pintype "passive"))
      (node (ref "C51") (pin "2") (pinfunction "2_2") (pintype "passive"))
      (node (ref "C52") (pin "2") (pinfunction "2_2") (pintype "passive"))
      (node (ref "C53") (pin "-") (pinfunction "-_-") (pintype "passive"))
      (node (ref "C54") (pin "2") (pinfunction "2_2") (pintype "passive"))
      (node (ref "C55") (pin "-") (pinfunction "-_-") (pintype "passive"))
      (node (ref "C56") (pin "2") (pinfunction "2_2") (pintype "passive"))
      (node (ref "C57") (pin "2") (pinfunction "2_2") (pintype "passive"))
      (node (ref "C58") (pin "2") (pinfunction "2_2") (pintype "passive"))
      (node (ref "C59") (pin "1") (pinfunction "1_1") (pintype "passive"))
      (node (ref "C6") (pin "1") (pinfunction "1_1") (pintype "passive"))
      (node (ref "C60") (pin "2") (pinfunction "2_2") (pintype "passive"))
      (node (ref "C62") (pin "2") (pinfunction "2_2") (pintype "passive"))
      (node (ref "C63") (pin "2") (pinfunction "2_2") (pintype "passive"))
      (node (ref "C65") (pin "2") (pinfunction "2_2") (pintype "passive"))
      (node (ref "C66") (pin "2") (pinfunction "2_2") (pintype "passive"))
      (node (ref "C67") (pin "1") (pinfunction "1_1") (pintype "passive"))
      (node (ref "C68") (pin "-") (pinfunction "-_-") (pintype "passive"))
      (node (ref "C69") (pin "2") (pinfunction "2_2") (pintype "passive"))
      (node (ref "C7") (pin "1") (pinfunction "1_1") (pintype "passive"))
      (node (ref "C71") (pin "1") (pinfunction "1_1") (pintype "passive"))
      (node (ref "C72") (pin "2") (pinfunction "2_2") (pintype "passive"))
      (node (ref "C73") (pin "2") (pinfunction "2_2") (pintype "passive"))
      (node (ref "C74") (pin "1") (pinfunction "1_1") (pintype "passive"))
      (node (ref "C75") (pin "1") (pinfunction "1_1") (pintype "passive"))
      (node (ref "C8") (pin "1") (pinfunction "1_1") (pintype "passive"))
      (node (ref "C9") (pin "1") (pinfunction "1_1") (pintype "passive"))
      (node (ref "COMPOSITE_VIDEO135") (pin "GND1") (pinfunction "GND_GND1") (pintype "power_in"))
      (node (ref "COMPOSITE_VIDEO135") (pin "GND2") (pinfunction "GND_GND2") (pintype "input"))
      (node (ref "COMPOSITE_VIDEO135") (pin "GND3") (pinfunction "GND_GND3") (pintype "input"))
      (node (ref "D2") (pin "1") (pinfunction "A_1") (pintype "passive"))
      (node (ref "D3") (pin "A") (pinfunction "1_A") (pintype "passive"))
      (node (ref "FET1") (pin "1") (pinfunction "G_1") (pintype "passive"))
      (node (ref "GND_PIN135") (pin "P$1") (pinfunction "PP_P$1") (pintype "passive"))
      (node (ref "GPIO_CON135") (pin "2") (pinfunction "2_2") (pintype "passive"))
      (node (ref "GPIO_CON135") (pin "40") (pinfunction "40_40") (pintype "passive"))
      (node (ref "JTAG135") (pin "3") (pinfunction "3_3") (pintype "passive"))
      (node (ref "L3") (pin "1") (pinfunction "1_1") (pintype "passive"))
      (node (ref "LINE_IN135") (pin "5") (pinfunction "5_5") (pintype "bidirectional"))
      (node (ref "LIPO_BAT135") (pin "2") (pinfunction "2_2") (pintype "passive"))
      (node (ref "PGM_FUSES135") (pin "3") (pinfunction "3_3") (pintype "passive"))
      (node (ref "PWR_JACK135") (pin "-") (pinfunction "-_-") (pintype "passive"))
      (node (ref "PWR_JACK135") (pin "--") (pinfunction "--_--") (pintype "passive"))
      (node (ref "PWR_LED135") (pin "C") (pinfunction "C_C") (pintype "passive"))
      (node (ref "R10") (pin "2") (pinfunction "2_2") (pintype "passive"))
      (node (ref "R14") (pin "1") (pinfunction "1_1") (pintype "passive"))
      (node (ref "R19") (pin "1") (pinfunction "1_1") (pintype "passive"))
      (node (ref "R2") (pin "1") (pinfunction "1_1") (pintype "passive"))
      (node (ref "R20") (pin "2") (pinfunction "2_2") (pintype "passive"))
      (node (ref "R27") (pin "1") (pinfunction "1_1") (pintype "passive"))
      (node (ref "R28") (pin "1") (pinfunction "1_1") (pintype "passive"))
      (node (ref "R29") (pin "1") (pinfunction "1_1") (pintype "passive"))
      (node (ref "R31") (pin "1") (pinfunction "1_1") (pintype "passive"))
      (node (ref "R32") (pin "1") (pinfunction "1_1") (pintype "passive"))
      (node (ref "R33") (pin "1") (pinfunction "1_1") (pintype "passive"))
      (node (ref "R34") (pin "1") (pinfunction "1_1") (pintype "passive"))
      (node (ref "R35") (pin "1") (pinfunction "1_1") (pintype "passive"))
      (node (ref "R36") (pin "1") (pinfunction "1_1") (pintype "passive"))
      (node (ref "R37") (pin "1") (pinfunction "1_1") (pintype "passive"))
      (node (ref "R38") (pin "1") (pinfunction "1_1") (pintype "passive"))
      (node (ref "R39") (pin "2") (pinfunction "2_2") (pintype "passive"))
      (node (ref "R4") (pin "2") (pinfunction "2_2") (pintype "passive"))
      (node (ref "R41") (pin "2") (pinfunction "2_2") (pintype "passive"))
      (node (ref "R43") (pin "2") (pinfunction "2_2") (pintype "passive"))
      (node (ref "R7") (pin "1") (pinfunction "1_1") (pintype "passive"))
      (node (ref "R8") (pin "1") (pinfunction "1_1") (pintype "passive"))
      (node (ref "RM1") (pin "1.1") (pinfunction "1_1.1") (pintype "passive"))
      (node (ref "RM2") (pin "1.1") (pinfunction "1.1_1.1") (pintype "passive"))
      (node (ref "RM2") (pin "2.1") (pinfunction "2.1_2.1") (pintype "passive"))
      (node (ref "RM2") (pin "3.1") (pinfunction "3.1_3.1") (pintype "passive"))
      (node (ref "RM2") (pin "4.1") (pinfunction "4.1_4.1") (pintype "passive"))
      (node (ref "SD135") (pin "6") (pinfunction "VSS_6") (pintype "power_in"))
      (node (ref "SJTAG135") (pin "2") (pinfunction "2_2") (pintype "passive"))
      (node (ref "T1") (pin "1") (pinfunction "B_1") (pintype "passive"))
      (node (ref "T1") (pin "2") (pinfunction "E_2") (pintype "passive"))
      (node (ref "T2") (pin "2") (pinfunction "E_2") (pintype "passive"))
      (node (ref "U1") (pin "105") (pinfunction "VSSA4_105") (pintype "power_in"))
      (node (ref "U1") (pin "112") (pinfunction "VSSA1_112") (pintype "power_in"))
      (node (ref "U1") (pin "118") (pinfunction "VSSA2_118") (pintype "power_in"))
      (node (ref "U1") (pin "30") (pinfunction "VSSD1_30") (pintype "power_in"))
      (node (ref "U1") (pin "35") (pinfunction "VSSD2_35") (pintype "power_in"))
      (node (ref "U1") (pin "98") (pinfunction "DCDC_GND_98") (pintype "power_in"))
      (node (ref "U2") (pin "12") (pinfunction "VSSQ2_12") (pintype "power_in"))
      (node (ref "U2") (pin "34") (pinfunction "VSS1_34") (pintype "power_in"))
      (node (ref "U2") (pin "48") (pinfunction "VSS2_48") (pintype "power_in"))
      (node (ref "U2") (pin "52") (pinfunction "VSSQ3_52") (pintype "power_in"))
      (node (ref "U2") (pin "58") (pinfunction "VSSQ4_58") (pintype "power_in"))
      (node (ref "U2") (pin "6") (pinfunction "VSSQ1_6") (pintype "power_in"))
      (node (ref "U2") (pin "64") (pinfunction "VSSQ5_64") (pintype "power_in"))
      (node (ref "U2") (pin "66") (pinfunction "VSS3_66") (pintype "power_in"))
      (node (ref "U3") (pin "2") (pinfunction "GND_2") (pintype "power_in"))
      (node (ref "U4") (pin "14") (pinfunction "TEST_14") (pintype "input"))
      (node (ref "U4") (pin "15") (pinfunction "GND_15") (pintype "power_in"))
      (node (ref "U5") (pin "4") (pinfunction "GND_4") (pintype "bidirectional"))
      (node (ref "U6") (pin "2") (pinfunction "GND_2") (pintype "bidirectional"))
      (node (ref "UEXT135") (pin "2") (pinfunction "2_2") (pintype "passive"))
      (node (ref "USB_HOST1") (pin "4") (pinfunction "4_4") (pintype "passive"))
      (node (ref "USB_HOST2") (pin "4") (pinfunction "4_4") (pintype "passive"))
      (node (ref "USB_HOST3") (pin "4") (pinfunction "4_4") (pintype "passive"))
      (node (ref "U_DEBUG135") (pin "3") (pinfunction "3_3") (pintype "passive"))
      (node (ref "WIFI135") (pin "4") (pinfunction "4_4") (pintype "passive"))
    )
    (net (code "113") (name "Net-(3.3V_E135-Pad1)") (class "Default")
      (node (ref "3.3V_E135") (pin "1") (pinfunction "1_1") (pintype "passive"))
      (node (ref "C64") (pin "1") (pinfunction "1_1") (pintype "passive"))
      (node (ref "C73") (pin "1") (pinfunction "1_1") (pintype "passive"))
      (node (ref "L5") (pin "2") (pinfunction "2_2") (pintype "passive"))
      (node (ref "R46") (pin "1") (pinfunction "1_1") (pintype "passive"))
    )
    (net (code "114") (name "Net-(5V_E135-Pad1)") (class "Default")
      (node (ref "5V_E135") (pin "1") (pinfunction "1_1") (pintype "passive"))
      (node (ref "C62") (pin "1") (pinfunction "1_1") (pintype "passive"))
      (node (ref "C72") (pin "1") (pinfunction "1_1") (pintype "passive"))
      (node (ref "L2") (pin "2") (pinfunction "2_2") (pintype "passive"))
      (node (ref "R3") (pin "2") (pinfunction "2_2") (pintype "passive"))
    )
    (net (code "115") (name "Net-(C27-Pad1)") (class "Default")
      (node (ref "C27") (pin "1") (pinfunction "1_1") (pintype "passive"))
      (node (ref "R5") (pin "1") (pinfunction "1_1") (pintype "passive"))
      (node (ref "R8") (pin "2") (pinfunction "2_2") (pintype "passive"))
    )
    (net (code "116") (name "Net-(C28-Pad1)") (class "Default")
      (node (ref "C28") (pin "1") (pinfunction "1_1") (pintype "passive"))
      (node (ref "R6") (pin "1") (pinfunction "1_1") (pintype "passive"))
      (node (ref "R7") (pin "2") (pinfunction "2_2") (pintype "passive"))
    )
    (net (code "117") (name "Net-(C40-Pad1)") (class "Default")
      (node (ref "C40") (pin "1") (pinfunction "1_1") (pintype "passive"))
      (node (ref "R24") (pin "1") (pinfunction "1_1") (pintype "passive"))
    )
    (net (code "118") (name "Net-(C44-Pad1)") (class "Default")
      (node (ref "C44") (pin "1") (pinfunction "1_1") (pintype "passive"))
      (node (ref "C45") (pin "1") (pinfunction "1_1") (pintype "passive"))
      (node (ref "C46") (pin "1") (pinfunction "1_1") (pintype "passive"))
      (node (ref "L7") (pin "2") (pinfunction "2_2") (pintype "passive"))
      (node (ref "U4") (pin "1") (pinfunction "AVDD_1") (pintype "power_in"))
      (node (ref "U4") (pin "10") (pinfunction "AVDD_10") (pintype "power_in"))
      (node (ref "U4") (pin "5") (pinfunction "AVDD_5") (pintype "power_in"))
    )
    (net (code "119") (name "Net-(C52-Pad1)") (class "Default")
      (node (ref "C52") (pin "1") (pinfunction "1_1") (pintype "passive"))
      (node (ref "L8") (pin "2") (pinfunction "2_2") (pintype "passive"))
      (node (ref "USB_HOST1") (pin "1") (pinfunction "1_1") (pintype "passive"))
    )
    (net (code "120") (name "Net-(C54-Pad1)") (class "Default")
      (node (ref "C54") (pin "1") (pinfunction "1_1") (pintype "passive"))
      (node (ref "L4") (pin "2") (pinfunction "2_2") (pintype "passive"))
      (node (ref "USB_HOST2") (pin "1") (pinfunction "1_1") (pintype "passive"))
    )
    (net (code "121") (name "Net-(C56-Pad1)") (class "Default")
      (node (ref "C56") (pin "1") (pinfunction "1_1") (pintype "passive"))
      (node (ref "L9") (pin "2") (pinfunction "2_2") (pintype "passive"))
      (node (ref "USB_HOST3") (pin "1") (pinfunction "1_1") (pintype "passive"))
    )
    (net (code "122") (name "Net-(C57-Pad1)") (class "Default")
      (node (ref "C57") (pin "1") (pinfunction "1_1") (pintype "passive"))
      (node (ref "C58") (pin "1") (pinfunction "1_1") (pintype "passive"))
      (node (ref "PWR_SEL135") (pin "2") (pinfunction "2_2") (pintype "passive"))
      (node (ref "WIFI135") (pin "1") (pinfunction "1_1") (pintype "passive"))
    )
    (net (code "123") (name "Net-(C61-Pad2)") (class "Default")
      (node (ref "C61") (pin "2") (pinfunction "2_2") (pintype "passive"))
      (node (ref "R43") (pin "1") (pinfunction "1_1") (pintype "passive"))
    )
    (net (code "124") (name "Net-(D00_H135-Pad1)") (class "Default")
      (node (ref "D00_H135") (pin "1") (pinfunction "1_1") (pintype "passive"))
      (node (ref "RM3") (pin "4.2") (pinfunction "4.2_4.2") (pintype "passive"))
    )
    (net (code "125") (name "Net-(D1-C)") (class "Default")
      (node (ref "C10") (pin "2") (pinfunction "2_2") (pintype "passive"))
      (node (ref "C9") (pin "2") (pinfunction "2_2") (pintype "passive"))
      (node (ref "D1") (pin "K") (pinfunction "C_K") (pintype "passive"))
      (node (ref "U1") (pin "101") (pinfunction "VDD4P2_101") (pintype "power_in"))
    )
    (net (code "126") (name "Net-(D01_H135-Pad1)") (class "Default")
      (node (ref "D01_H135") (pin "1") (pinfunction "1_1") (pintype "passive"))
      (node (ref "RM3") (pin "3.2") (pinfunction "3.2_3.2") (pintype "passive"))
    )
    (net (code "127") (name "Net-(D2-AK)") (class "Default")
      (node (ref "C66") (pin "1") (pinfunction "1_1") (pintype "passive"))
      (node (ref "COMPOSITE_VIDEO135") (pin "IO") (pinfunction "IO_IO") (pintype "bidirectional"))
      (node (ref "D2") (pin "3") (pinfunction "AK_3") (pintype "passive"))
      (node (ref "R26") (pin "2") (pinfunction "1.2_2") (pintype "passive"))
    )
    (net (code "128") (name "Net-(D02_H135-Pad1)") (class "Default")
      (node (ref "D02_H135") (pin "1") (pinfunction "1_1") (pintype "passive"))
      (node (ref "RM3") (pin "2.2") (pinfunction "2.2_2.2") (pintype "passive"))
    )
    (net (code "129") (name "Net-(D03_H135-Pad1)") (class "Default")
      (node (ref "D03_H135") (pin "1") (pinfunction "1_1") (pintype "passive"))
      (node (ref "RM3") (pin "1.2") (pinfunction "1.2_1.2") (pintype "passive"))
    )
    (net (code "130") (name "Net-(FET1-D)") (class "Default")
      (node (ref "FET1") (pin "3") (pinfunction "D_3") (pintype "passive"))
      (node (ref "PWR_JACK135") (pin "+") (pinfunction "+_+") (pintype "passive"))
    )
    (net (code "131") (name "Net-(LED1-PadC)") (class "Default")
      (node (ref "LED1") (pin "C") (pinfunction "C_C") (pintype "passive"))
      (node (ref "R2") (pin "2") (pinfunction "2_2") (pintype "passive"))
    )
    (net (code "132") (name "Net-(LINE_IN135-Pad2)") (class "Default")
      (node (ref "LINE_IN135") (pin "2") (pinfunction "2_2") (pintype "bidirectional"))
      (node (ref "R5") (pin "2") (pinfunction "2_2") (pintype "passive"))
    )
    (net (code "133") (name "Net-(LINE_IN135-Pad3)") (class "Default")
      (node (ref "LINE_IN135") (pin "3") (pinfunction "3_3") (pintype "bidirectional"))
      (node (ref "R6") (pin "2") (pinfunction "2_2") (pintype "passive"))
    )
    (net (code "134") (name "Net-(PWR_LED135-PadA)") (class "Default")
      (node (ref "PWR_LED135") (pin "A") (pinfunction "A_A") (pintype "passive"))
      (node (ref "R22") (pin "2") (pinfunction "2_2") (pintype "passive"))
    )
    (net (code "135") (name "Net-(R25-Pad1)") (class "Default")
      (node (ref "R25") (pin "1") (pinfunction "1_1") (pintype "passive"))
      (node (ref "REC135") (pin "1") (pinfunction "1_1") (pintype "passive"))
    )
    (net (code "136") (name "Net-(R26-1.1)") (class "Default")
      (node (ref "R26") (pin "1") (pinfunction "1.1_1") (pintype "passive"))
      (node (ref "U1") (pin "104") (pinfunction "VDAC1_104") (pintype "output"))
    )
    (net (code "137") (name "Net-(T2-B)") (class "Default")
      (node (ref "R10") (pin "1") (pinfunction "1_1") (pintype "passive"))
      (node (ref "R42") (pin "1") (pinfunction "1_1") (pintype "passive"))
      (node (ref "T2") (pin "1") (pinfunction "B_1") (pintype "passive"))
    )
    (net (code "138") (name "Net-(U1-DCDC_LN1)") (class "Default")
      (node (ref "C74") (pin "2") (pinfunction "2_2") (pintype "passive"))
      (node (ref "L1") (pin "2") (pinfunction "2_2") (pintype "passive"))
      (node (ref "U1") (pin "97") (pinfunction "DCDC_LN1_97") (pintype "passive"))
    )
    (net (code "139") (name "Net-(U1-DCDC_LP)") (class "Default")
      (node (ref "C75") (pin "2") (pinfunction "2_2") (pintype "passive"))
      (node (ref "L1") (pin "1") (pinfunction "1_1") (pintype "passive"))
      (node (ref "U1") (pin "99") (pinfunction "DCDC_LP_99") (pintype "passive"))
    )
    (net (code "140") (name "Net-(U1-HPL)") (class "Default")
      (node (ref "HEADPHONES135") (pin "2") (pinfunction "2_2") (pintype "bidirectional"))
      (node (ref "R45") (pin "2") (pinfunction "2_2") (pintype "passive"))
      (node (ref "U1") (pin "113") (pinfunction "HPL_113") (pintype "output"))
    )
    (net (code "141") (name "Net-(U1-HPR)") (class "Default")
      (node (ref "HEADPHONES135") (pin "3") (pinfunction "3_3") (pintype "bidirectional"))
      (node (ref "R44") (pin "2") (pinfunction "2_2") (pintype "passive"))
      (node (ref "U1") (pin "109") (pinfunction "HPR_109") (pintype "output"))
    )
    (net (code "142") (name "Net-(U1-HP_VGND)") (class "Default")
      (node (ref "HEADPHONES135") (pin "5") (pinfunction "5_5") (pintype "bidirectional"))
      (node (ref "R44") (pin "1") (pinfunction "1_1") (pintype "passive"))
      (node (ref "R45") (pin "1") (pinfunction "1_1") (pintype "passive"))
      (node (ref "U1") (pin "111") (pinfunction "HP_VGND_111") (pintype "power_in"))
    )
    (net (code "143") (name "Net-(U1-LINE1_INL)") (class "Default")
      (node (ref "C27") (pin "2") (pinfunction "2_2") (pintype "passive"))
      (node (ref "U1") (pin "115") (pinfunction "LINE1_INL_115") (pintype "input"))
    )
    (net (code "144") (name "Net-(U1-LINE1_INR)") (class "Default")
      (node (ref "C28") (pin "2") (pinfunction "2_2") (pintype "passive"))
      (node (ref "U1") (pin "114") (pinfunction "LINE1_INR_114") (pintype "input"))
    )
    (net (code "145") (name "Net-(U1-VAG)") (class "Default")
      (node (ref "C26") (pin "2") (pinfunction "2_2") (pintype "passive"))
      (node (ref "U1") (pin "117") (pinfunction "VAG_117") (pintype "passive"))
    )
    (net (code "146") (name "Net-(U2-VREF)") (class "Default")
      (node (ref "C38") (pin "2") (pinfunction "2_2") (pintype "passive"))
      (node (ref "C39") (pin "2") (pinfunction "2_2") (pintype "passive"))
      (node (ref "R18") (pin "1") (pinfunction "1_1") (pintype "passive"))
      (node (ref "R19") (pin "2") (pinfunction "2_2") (pintype "passive"))
      (node (ref "U2") (pin "49") (pinfunction "VREF_49") (pintype "input"))
    )
    (net (code "147") (name "Net-(U3-ISET)") (class "Default")
      (node (ref "R27") (pin "2") (pinfunction "2_2") (pintype "passive"))
      (node (ref "U3") (pin "3") (pinfunction "ISET_3") (pintype "bidirectional"))
    )
    (net (code "148") (name "Net-(U3-OUT)") (class "Default")
      (node (ref "C48") (pin "+") (pinfunction "+_+") (pintype "passive"))
      (node (ref "C53") (pin "+") (pinfunction "+_+") (pintype "passive"))
      (node (ref "C55") (pin "+") (pinfunction "+_+") (pintype "passive"))
      (node (ref "L4") (pin "1") (pinfunction "1_1") (pintype "passive"))
      (node (ref "L8") (pin "1") (pinfunction "1_1") (pintype "passive"))
      (node (ref "L9") (pin "1") (pinfunction "1_1") (pintype "passive"))
      (node (ref "U3") (pin "1") (pinfunction "OUT_1") (pintype "bidirectional"))
    )
    (net (code "149") (name "Net-(U4-#RESET)") (class "Default")
      (node (ref "C59") (pin "2") (pinfunction "2_2") (pintype "passive"))
      (node (ref "PGM_FUSES135") (pin "4") (pinfunction "4_4") (pintype "passive"))
      (node (ref "R39") (pin "1") (pinfunction "1_1") (pintype "passive"))
      (node (ref "R40") (pin "1") (pinfunction "1_1") (pintype "passive"))
      (node (ref "U4") (pin "13") (pinfunction "#RESET_13") (pintype "bidirectional"))
    )
    (net (code "150") (name "Net-(U4-DM1)") (class "Default")
      (node (ref "R31") (pin "2") (pinfunction "2_2") (pintype "passive"))
      (node (ref "U4") (pin "27") (pinfunction "DM1_27") (pintype "bidirectional"))
      (node (ref "USB_HOST1") (pin "2") (pinfunction "2_2") (pintype "passive"))
    )
    (net (code "151") (name "Net-(U4-DM2)") (class "Default")
      (node (ref "R33") (pin "2") (pinfunction "2_2") (pintype "passive"))
      (node (ref "U4") (pin "2") (pinfunction "DM2_2") (pintype "bidirectional"))
      (node (ref "USB_HOST2") (pin "2") (pinfunction "2_2") (pintype "passive"))
    )
    (net (code "152") (name "Net-(U4-DM3)") (class "Default")
      (node (ref "R35") (pin "2") (pinfunction "2_2") (pintype "passive"))
      (node (ref "U4") (pin "8") (pinfunction "DM3_8") (pintype "bidirectional"))
      (node (ref "USB_HOST3") (pin "2") (pinfunction "2_2") (pintype "passive"))
    )
    (net (code "153") (name "Net-(U4-DM4)") (class "Default")
      (node (ref "R37") (pin "2") (pinfunction "2_2") (pintype "passive"))
      (node (ref "U4") (pin "11") (pinfunction "DM4_11") (pintype "bidirectional"))
      (node (ref "WIFI135") (pin "2") (pinfunction "2_2") (pintype "passive"))
    )
    (net (code "154") (name "Net-(U4-DP1)") (class "Default")
      (node (ref "R32") (pin "2") (pinfunction "2_2") (pintype "passive"))
      (node (ref "U4") (pin "28") (pinfunction "DP1_28") (pintype "bidirectional"))
      (node (ref "USB_HOST1") (pin "3") (pinfunction "3_3") (pintype "passive"))
    )
    (net (code "155") (name "Net-(U4-DP2)") (class "Default")
      (node (ref "R34") (pin "2") (pinfunction "2_2") (pintype "passive"))
      (node (ref "U4") (pin "3") (pinfunction "DP2_3") (pintype "bidirectional"))
      (node (ref "USB_HOST2") (pin "3") (pinfunction "3_3") (pintype "passive"))
    )
    (net (code "156") (name "Net-(U4-DP3)") (class "Default")
      (node (ref "R36") (pin "2") (pinfunction "2_2") (pintype "passive"))
      (node (ref "U4") (pin "9") (pinfunction "DP3_9") (pintype "bidirectional"))
      (node (ref "USB_HOST3") (pin "3") (pinfunction "3_3") (pintype "passive"))
    )
    (net (code "157") (name "Net-(U4-DP4)") (class "Default")
      (node (ref "R38") (pin "2") (pinfunction "2_2") (pintype "passive"))
      (node (ref "U4") (pin "12") (pinfunction "DP4_12") (pintype "bidirectional"))
      (node (ref "WIFI135") (pin "3") (pinfunction "3_3") (pintype "passive"))
    )
    (net (code "158") (name "Net-(U4-DVDD)") (class "Default")
      (node (ref "C47") (pin "1") (pinfunction "1_1") (pintype "passive"))
      (node (ref "C49") (pin "1") (pinfunction "1_1") (pintype "passive"))
      (node (ref "L7") (pin "1") (pinfunction "1_1") (pintype "passive"))
      (node (ref "R30") (pin "1") (pinfunction "1_1") (pintype "passive"))
      (node (ref "U4") (pin "16") (pinfunction "DVDD_16") (pintype "power_in"))
      (node (ref "U4") (pin "24") (pinfunction "V33_24") (pintype "power_in"))
    )
    (net (code "159") (name "Net-(U4-PGANG)") (class "Default")
      (node (ref "R30") (pin "2") (pinfunction "2_2") (pintype "passive"))
      (node (ref "U4") (pin "18") (pinfunction "PGANG_18") (pintype "bidirectional"))
    )
    (net (code "160") (name "Net-(U4-RREF)") (class "Default")
      (node (ref "R29") (pin "2") (pinfunction "2_2") (pintype "passive"))
      (node (ref "U4") (pin "4") (pinfunction "RREF_4") (pintype "bidirectional"))
    )
    (net (code "161") (name "Net-(U5-BS)") (class "Default")
      (node (ref "C70") (pin "1") (pinfunction "1_1") (pintype "passive"))
      (node (ref "U5") (pin "1") (pinfunction "BS_1") (pintype "bidirectional"))
    )
    (net (code "162") (name "Net-(U5-COMP)") (class "Default")
      (node (ref "C61") (pin "1") (pinfunction "1_1") (pintype "passive"))
      (node (ref "U5") (pin "6") (pinfunction "COMP_6") (pintype "bidirectional"))
    )
    (net (code "163") (name "Net-(U5-EN)") (class "Default")
      (node (ref "R1") (pin "2") (pinfunction "2_2") (pintype "passive"))
      (node (ref "U5") (pin "7") (pinfunction "EN_7") (pintype "bidirectional"))
    )
    (net (code "164") (name "Net-(U5-FB)") (class "Default")
      (node (ref "R3") (pin "1") (pinfunction "1_1") (pintype "passive"))
      (node (ref "R4") (pin "1") (pinfunction "1_1") (pintype "passive"))
      (node (ref "U5") (pin "5") (pinfunction "FB_5") (pintype "bidirectional"))
    )
    (net (code "165") (name "Net-(U5-SS)") (class "Default")
      (node (ref "C69") (pin "1") (pinfunction "1_1") (pintype "passive"))
      (node (ref "U5") (pin "8") (pinfunction "SS_8") (pintype "bidirectional"))
    )
    (net (code "166") (name "Net-(U5-SW)") (class "Default")
      (node (ref "C70") (pin "2") (pinfunction "2_2") (pintype "passive"))
      (node (ref "L2") (pin "1") (pinfunction "1_1") (pintype "passive"))
      (node (ref "U5") (pin "3") (pinfunction "SW_3") (pintype "bidirectional"))
    )
    (net (code "167") (name "Net-(U6-FB)") (class "Default")
      (node (ref "C64") (pin "2") (pinfunction "2_2") (pintype "passive"))
      (node (ref "R41") (pin "1") (pinfunction "1_1") (pintype "passive"))
      (node (ref "R46") (pin "2") (pinfunction "2_2") (pintype "passive"))
      (node (ref "U6") (pin "5") (pinfunction "FB_5") (pintype "bidirectional"))
    )
    (net (code "168") (name "Net-(U6-LX)") (class "Default")
      (node (ref "L5") (pin "1") (pinfunction "1_1") (pintype "passive"))
      (node (ref "U6") (pin "3") (pinfunction "LX_3") (pintype "bidirectional"))
    )
    (net (code "169") (name "Net-(USB_HOST1-5)") (class "Default")
      (node (ref "L3") (pin "2") (pinfunction "2_2") (pintype "passive"))
      (node (ref "USB_HOST1") (pin "P$3") (pinfunction "5_P$3") (pintype "input"))
      (node (ref "USB_HOST1") (pin "P$4") (pinfunction "6_P$4") (pintype "input"))
      (node (ref "USB_HOST2") (pin "P$3") (pinfunction "5_P$3") (pintype "input"))
      (node (ref "USB_HOST2") (pin "P$4") (pinfunction "6_P$4") (pintype "input"))
      (node (ref "USB_HOST3") (pin "P$3") (pinfunction "5_P$3") (pintype "input"))
      (node (ref "USB_HOST3") (pin "P$4") (pinfunction "6_P$4") (pintype "input"))
    )
    (net (code "170") (name "VIN") (class "Default")
      (node (ref "C68") (pin "+") (pinfunction "+_+") (pintype "passive"))
      (node (ref "D3") (pin "C") (pinfunction "2_C") (pintype "passive"))
      (node (ref "FET1") (pin "2") (pinfunction "S_2") (pintype "passive"))
      (node (ref "GPIO_CON135") (pin "39") (pinfunction "39_39") (pintype "passive"))
      (node (ref "R1") (pin "1") (pinfunction "1_1") (pintype "passive"))
      (node (ref "U5") (pin "2") (pinfunction "IN_2") (pintype "bidirectional"))
    )
    (net (code "171") (name "unconnected-(HEADPHONES135-Pad1)") (class "Default")
      (node (ref "HEADPHONES135") (pin "1") (pinfunction "1_1") (pintype "bidirectional"))
    )
    (net (code "172") (name "unconnected-(HEADPHONES135-Pad4)") (class "Default")
      (node (ref "HEADPHONES135") (pin "4") (pinfunction "4_4") (pintype "bidirectional"))
    )
    (net (code "173") (name "unconnected-(LINE_IN135-Pad1)") (class "Default")
      (node (ref "LINE_IN135") (pin "1") (pinfunction "1_1") (pintype "bidirectional"))
    )
    (net (code "174") (name "unconnected-(LINE_IN135-Pad4)") (class "Default")
      (node (ref "LINE_IN135") (pin "4") (pinfunction "4_4") (pintype "bidirectional"))
    )
    (net (code "175") (name "unconnected-(U2-NC1-Pad14)") (class "Default")
      (node (ref "U2") (pin "14") (pinfunction "NC1_14") (pintype "no_connect"))
    )
    (net (code "176") (name "unconnected-(U2-NC2-Pad17)") (class "Default")
      (node (ref "U2") (pin "17") (pinfunction "NC2_17") (pintype "no_connect"))
    )
    (net (code "177") (name "unconnected-(U2-NC3-Pad19)") (class "Default")
      (node (ref "U2") (pin "19") (pinfunction "NC3_19") (pintype "no_connect"))
    )
    (net (code "178") (name "unconnected-(U2-NC4-Pad25)") (class "Default")
      (node (ref "U2") (pin "25") (pinfunction "NC4_25") (pintype "no_connect"))
    )
    (net (code "179") (name "unconnected-(U2-NC5-Pad43)") (class "Default")
      (node (ref "U2") (pin "43") (pinfunction "NC5_43") (pintype "no_connect"))
    )
    (net (code "180") (name "unconnected-(U2-NC6-Pad50)") (class "Default")
      (node (ref "U2") (pin "50") (pinfunction "NC6_50") (pintype "no_connect"))
    )
    (net (code "181") (name "unconnected-(U2-NC7-Pad53)") (class "Default")
      (node (ref "U2") (pin "53") (pinfunction "NC7_53") (pintype "no_connect"))
    )
    (net (code "182") (name "unconnected-(U4-#OVCUR1-Pad21)") (class "Default")
      (node (ref "U4") (pin "21") (pinfunction "#OVCUR1_21") (pintype "bidirectional"))
    )
    (net (code "183") (name "unconnected-(U4-#OVCUR2-Pad19)") (class "Default")
      (node (ref "U4") (pin "19") (pinfunction "#OVCUR2_19") (pintype "bidirectional"))
    )
    (net (code "184") (name "unconnected-(U4-#PWREN1-Pad22)") (class "Default")
      (node (ref "U4") (pin "22") (pinfunction "#PWREN1_22") (pintype "output"))
    )
    (net (code "185") (name "unconnected-(U4-#PWREN2-Pad20)") (class "Default")
      (node (ref "U4") (pin "20") (pinfunction "#PWREN2_20") (pintype "output"))
    )
    (net (code "186") (name "unconnected-(U4-PSELF-Pad17)") (class "Default")
      (node (ref "U4") (pin "17") (pinfunction "PSELF_17") (pintype "bidirectional"))
    )
  )
)
